# TPadTabletBattery.net
KiCad netlist of a schematic drawn in EAGLE
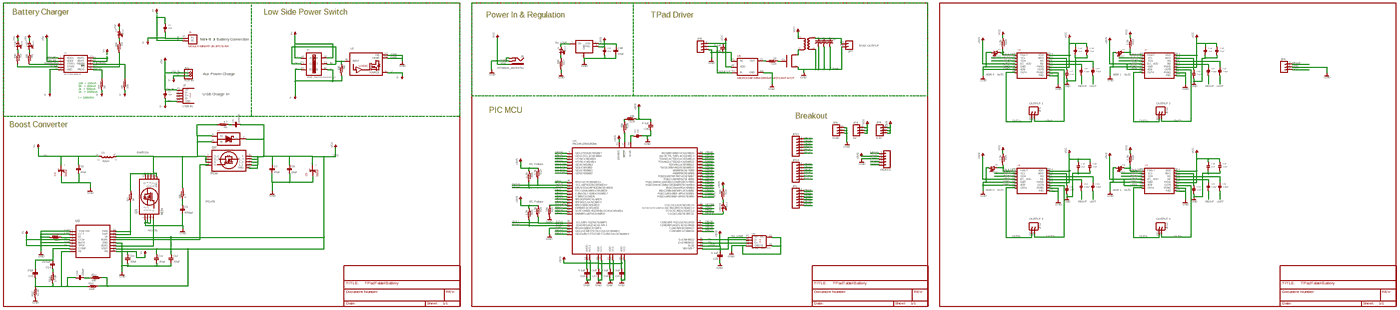
[diagram p0: schematic, sheet 1, overview]
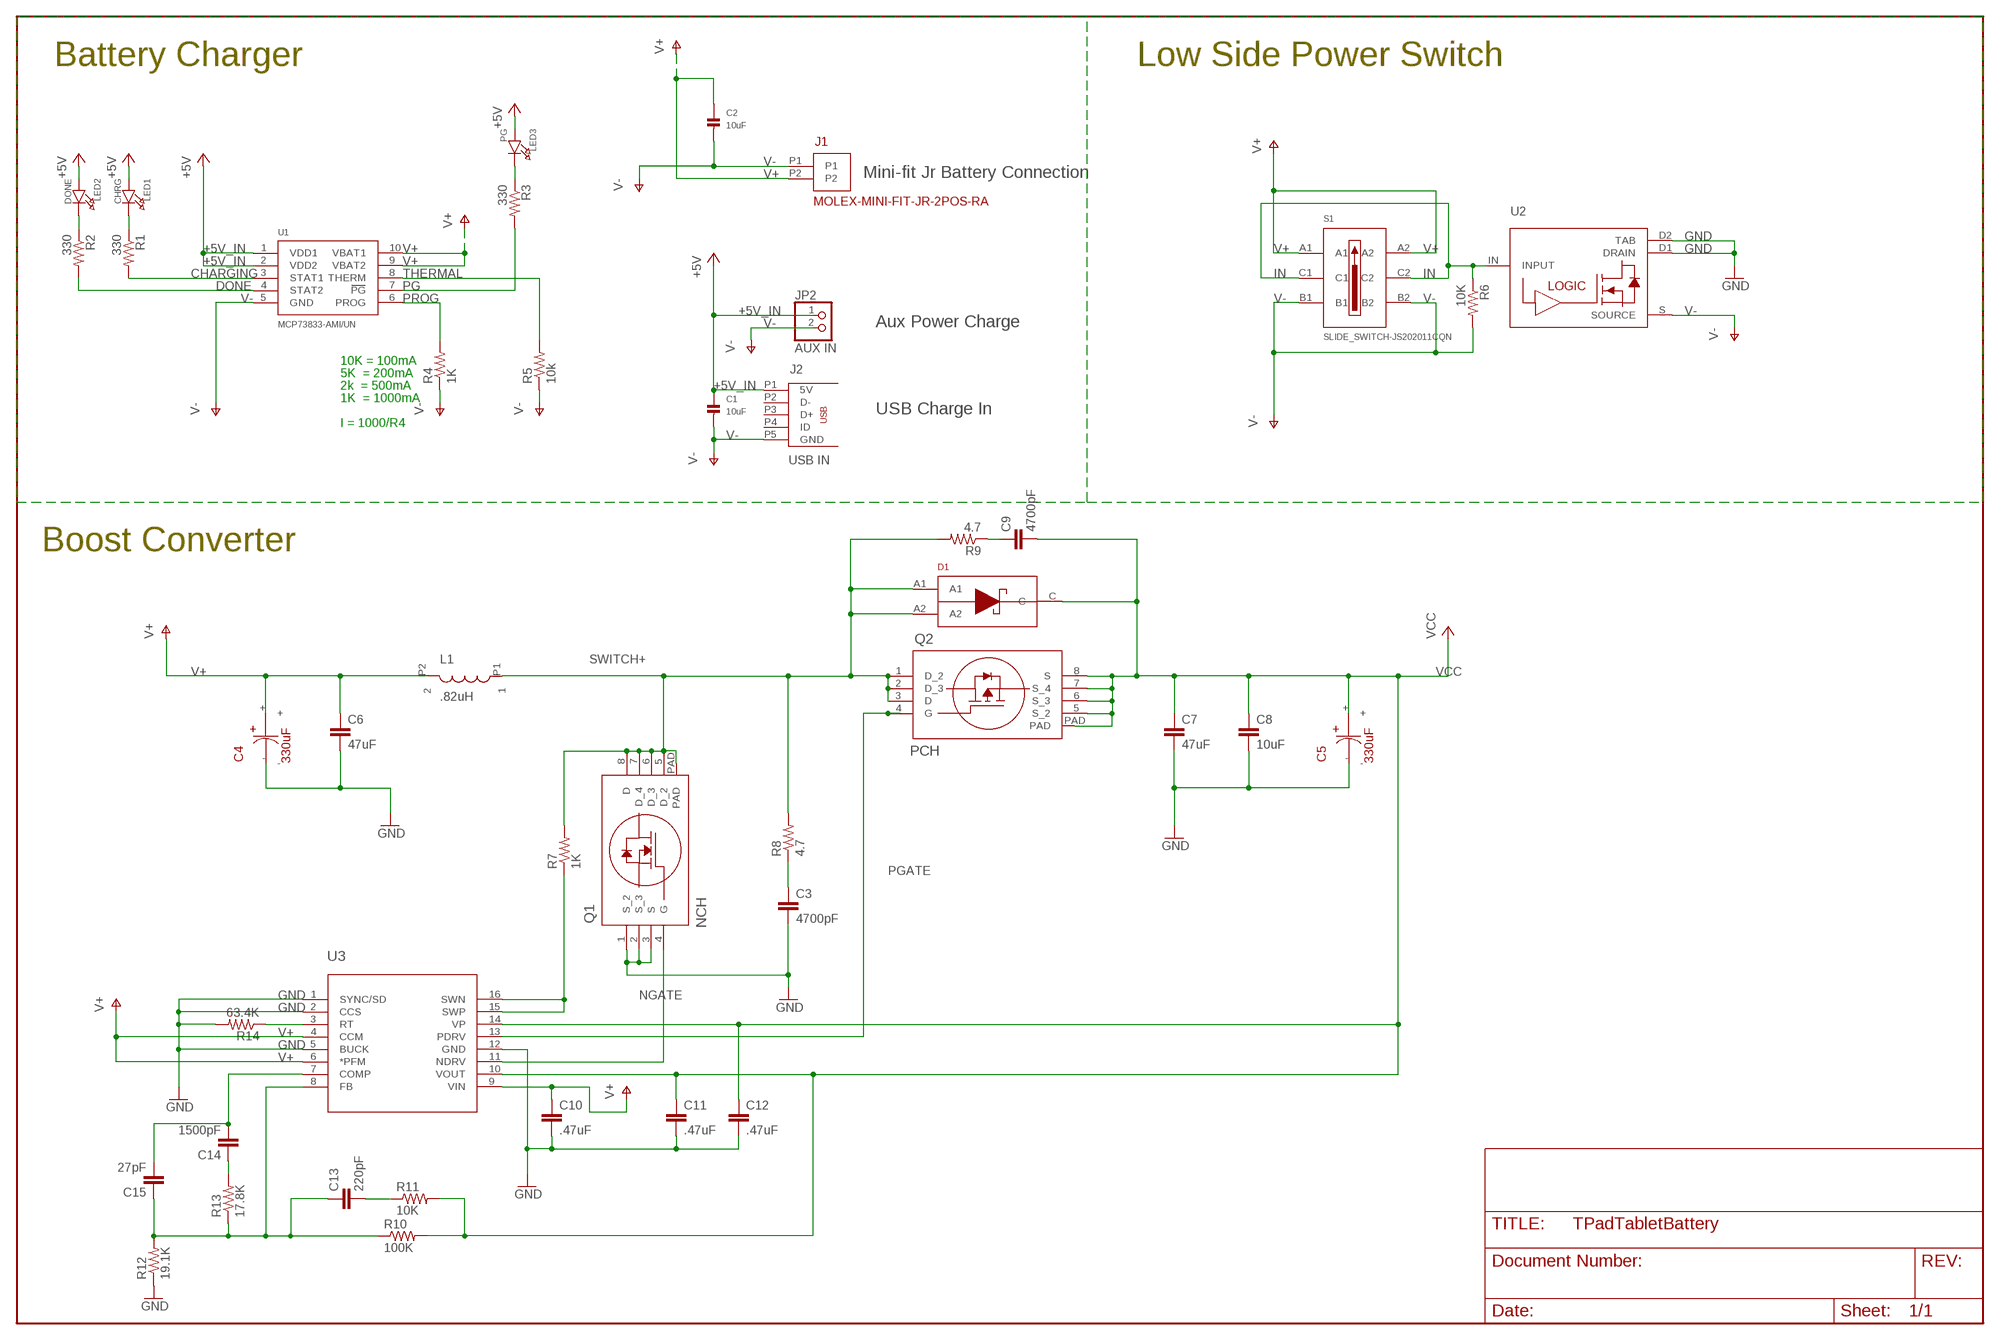
[diagram p1: schematic, sheet 1, part 1 of 4]
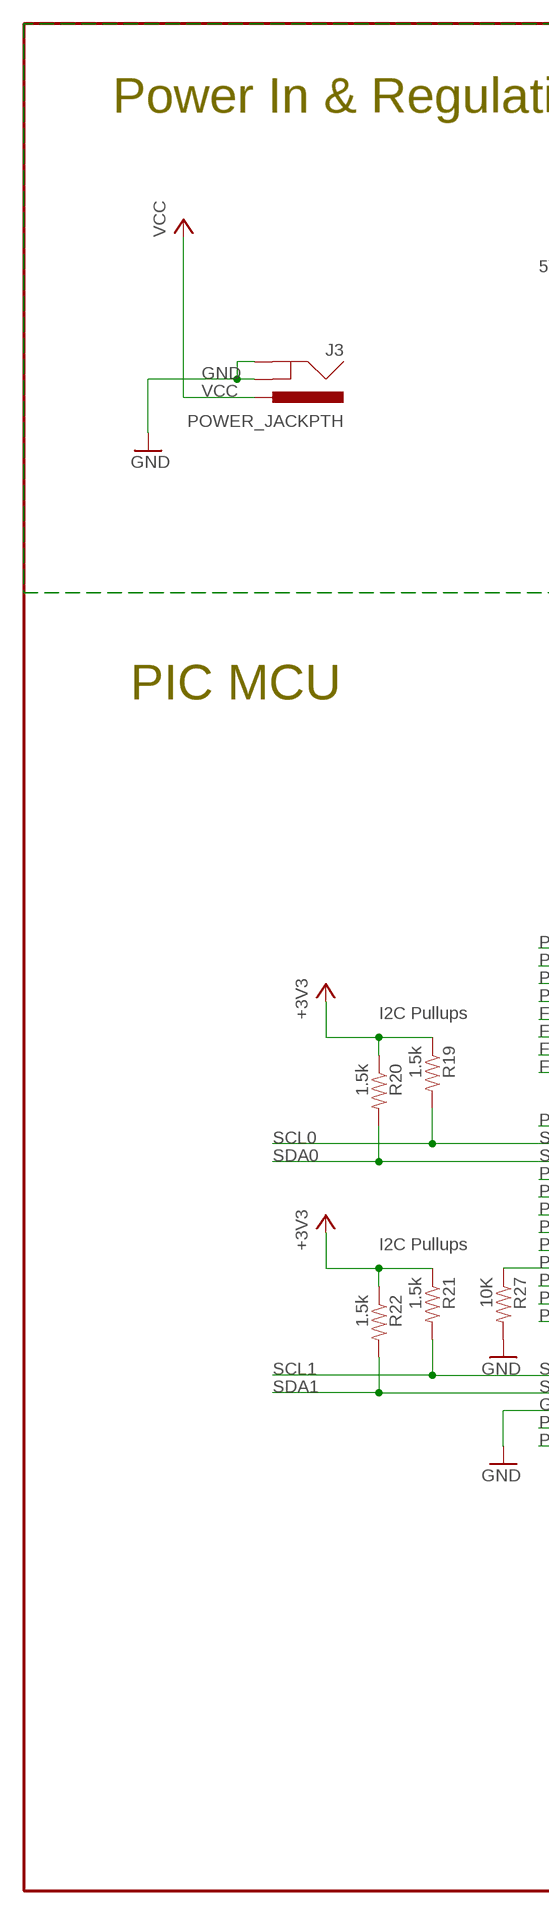
[diagram p2: schematic, sheet 1, part 2 of 4]
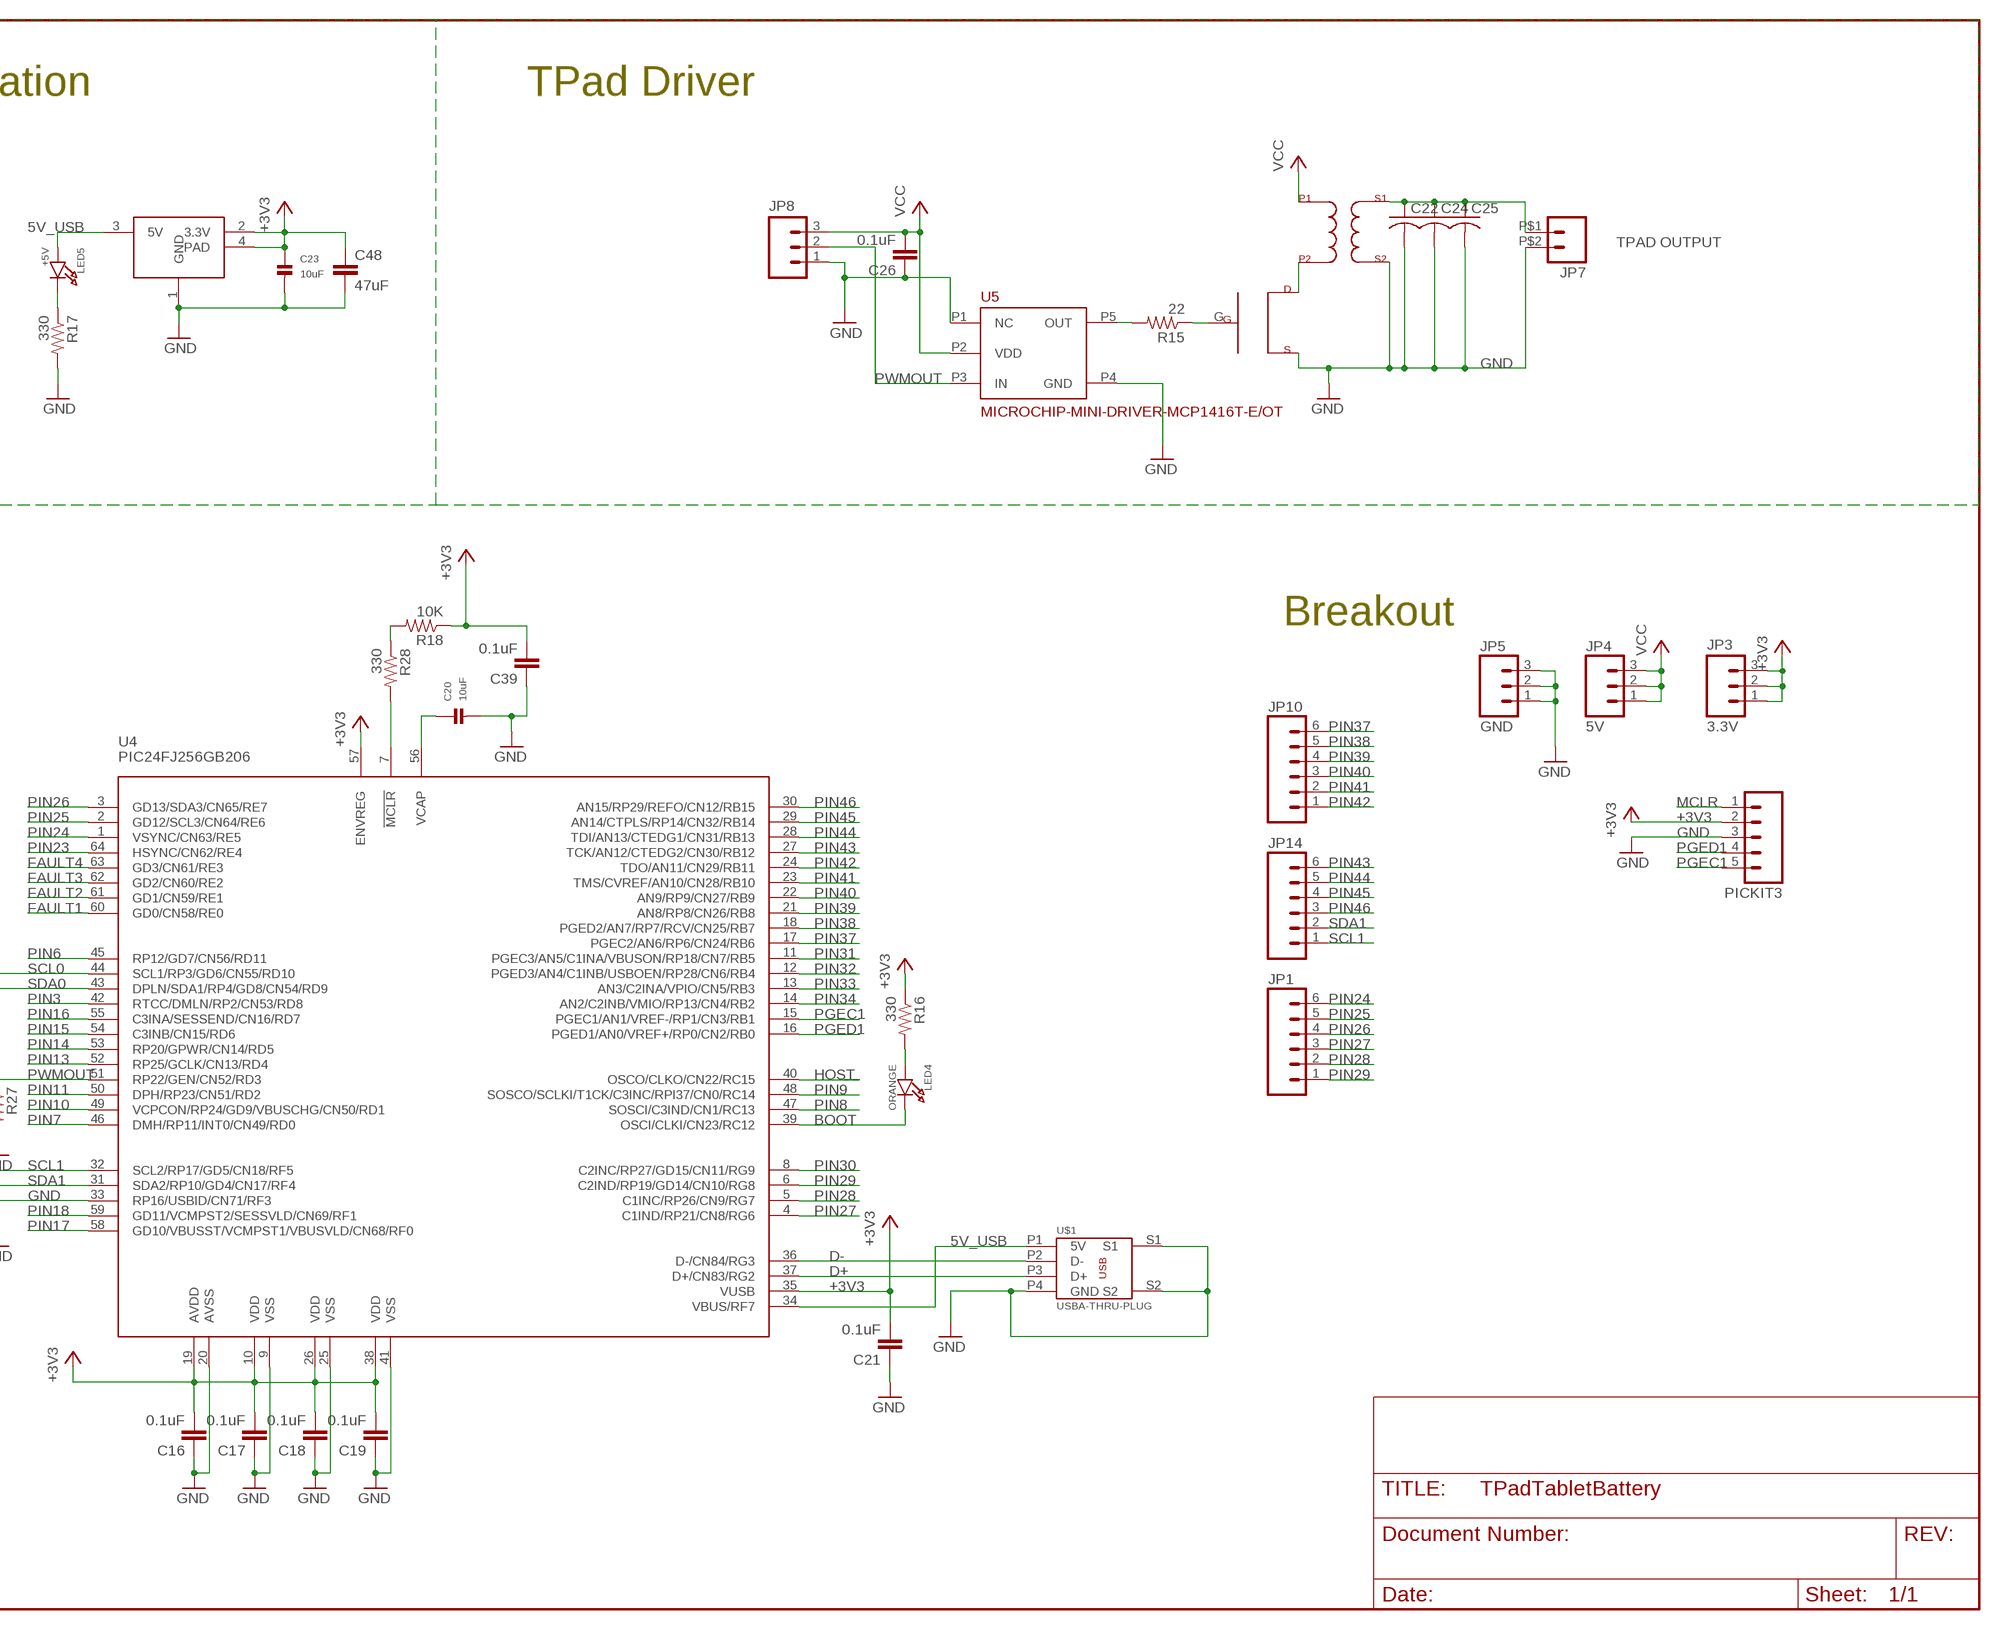
[diagram p3: schematic, sheet 1, part 3 of 4]
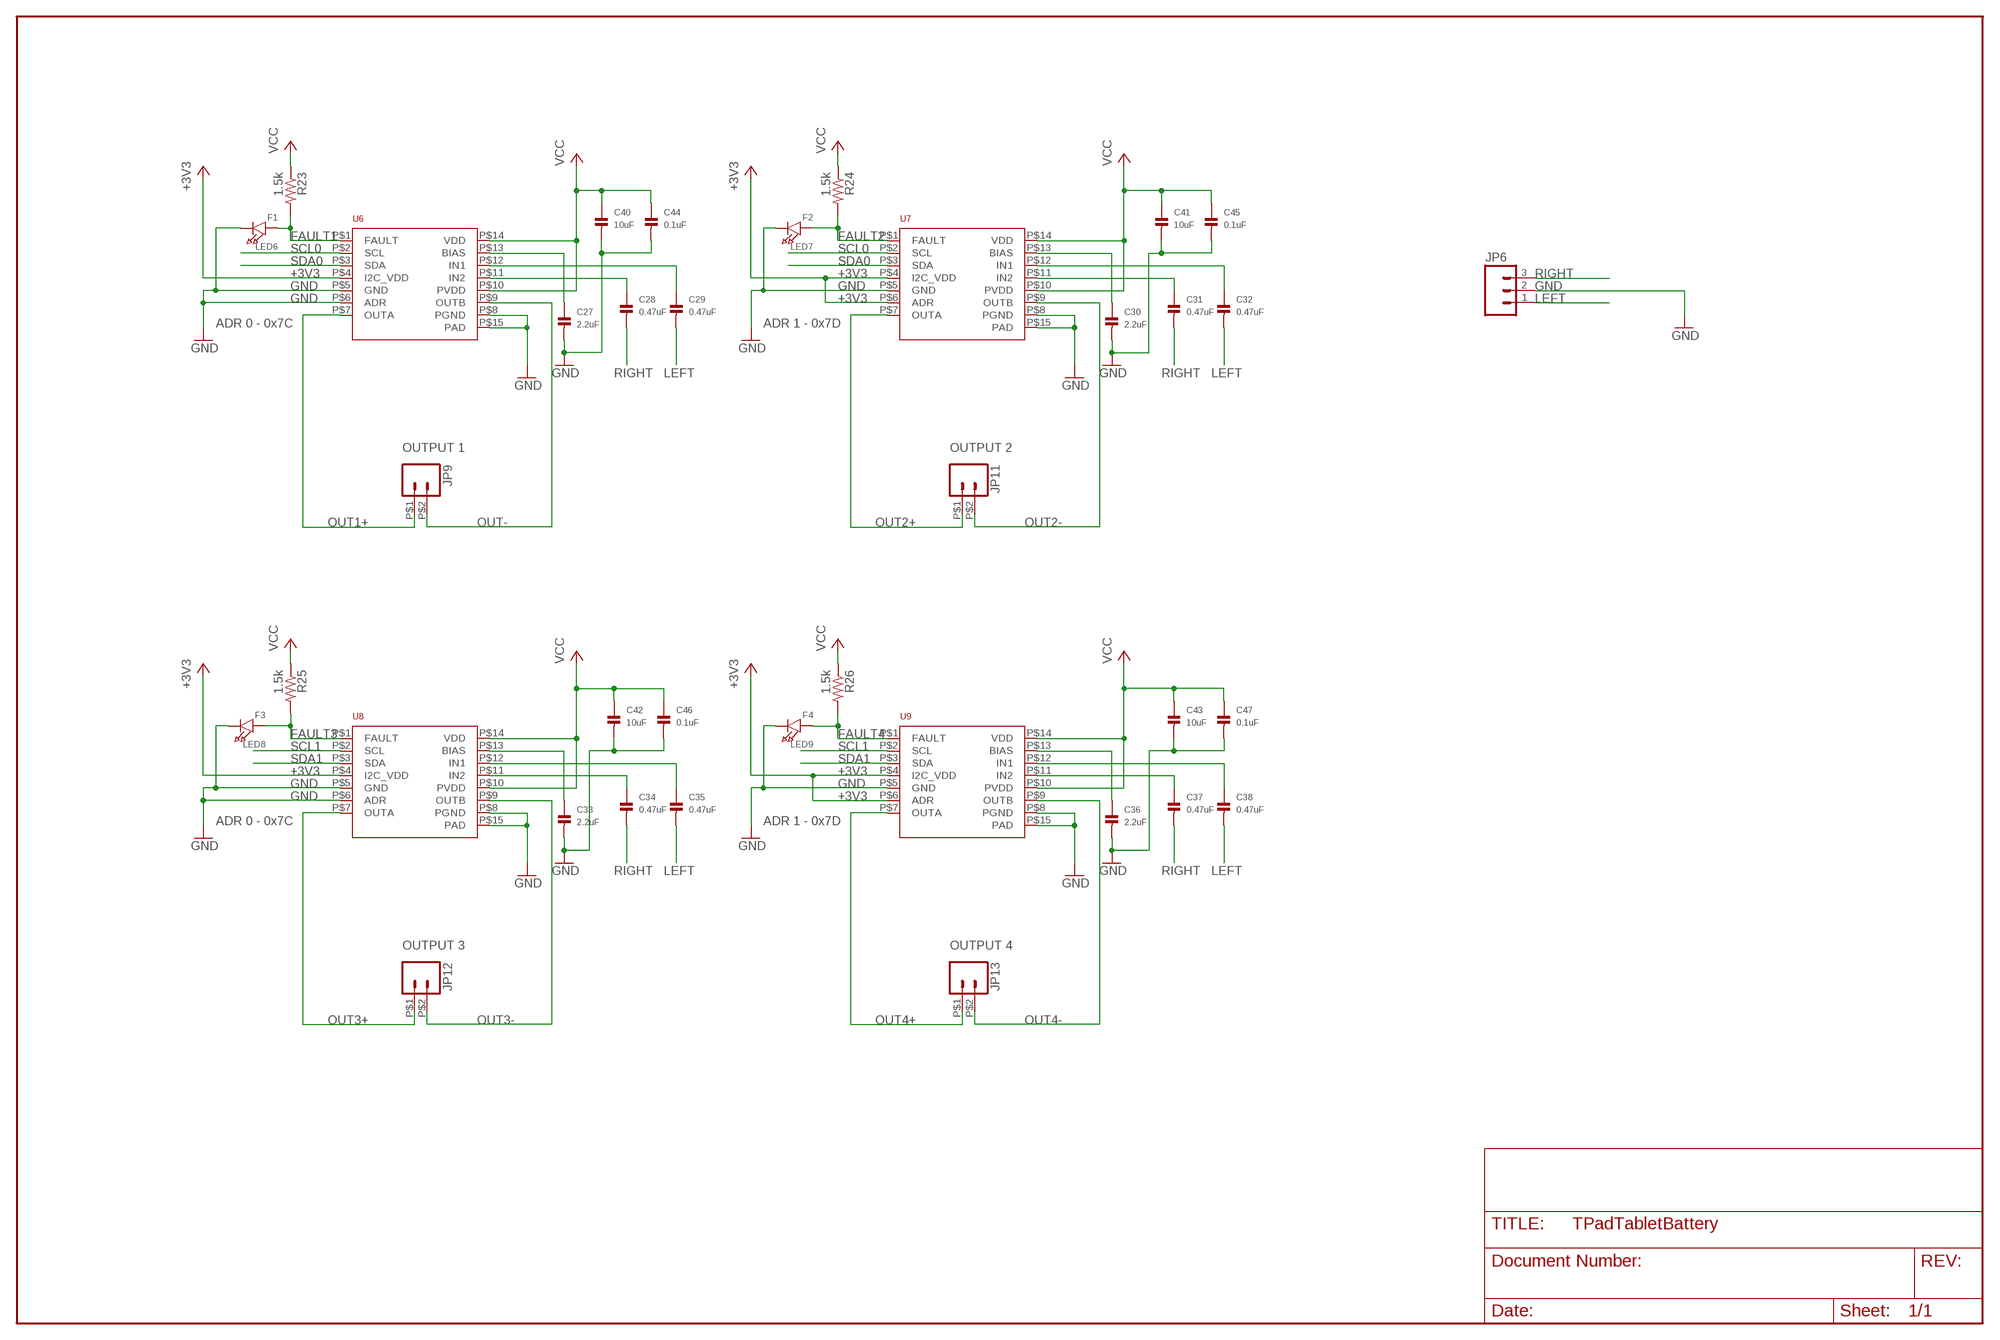
[diagram p4: schematic, sheet 1, part 4 of 4]

(export (version "E")
  (design (tool "Eeschema 10.0.6"))
  (components
    (comp (ref "C1")
      (value "10uF")
      (footprint "eagle-import:MICROBUILDER_0805")
      (libsource (lib "eagle-import") (part "MICROBUILDER_CAP_CERAMIC0805"))
    )
    (comp (ref "C2")
      (value "10uF")
      (footprint "eagle-import:MICROBUILDER_0805")
      (libsource (lib "eagle-import") (part "MICROBUILDER_CAP_CERAMIC0805"))
    )
    (comp (ref "C3")
      (value "4700pF")
      (footprint "eagle-import:0603-CAP")
      (libsource (lib "eagle-import") (part "CAP0603-CAP"))
    )
    (comp (ref "C4")
      (value "330uF")
      (footprint "eagle-import:330UF_POSCAP")
      (libsource (lib "eagle-import") (part "330UF_POSCAP"))
    )
    (comp (ref "C5")
      (value "330uF")
      (footprint "eagle-import:330UF_POSCAP")
      (libsource (lib "eagle-import") (part "330UF_POSCAP"))
    )
    (comp (ref "C6")
      (value "47uF")
      (footprint "eagle-import:1210")
      (libsource (lib "eagle-import") (part "CAP1210"))
    )
    (comp (ref "C7")
      (value "47uF")
      (footprint "eagle-import:1210")
      (libsource (lib "eagle-import") (part "CAP1210"))
    )
    (comp (ref "C8")
      (value "10uF")
      (footprint "eagle-import:0805")
      (libsource (lib "eagle-import") (part "CAP0805"))
    )
    (comp (ref "C9")
      (value "4700pF")
      (footprint "eagle-import:0603-CAP")
      (libsource (lib "eagle-import") (part "CAP0603-CAP"))
    )
    (comp (ref "C10")
      (value ".47uF")
      (footprint "eagle-import:0603-CAP")
      (libsource (lib "eagle-import") (part "CAP0603-CAP"))
    )
    (comp (ref "C11")
      (value ".47uF")
      (footprint "eagle-import:0603-CAP")
      (libsource (lib "eagle-import") (part "CAP0603-CAP"))
    )
    (comp (ref "C12")
      (value ".47uF")
      (footprint "eagle-import:0603-CAP")
      (libsource (lib "eagle-import") (part "CAP0603-CAP"))
    )
    (comp (ref "C13")
      (value "220pF")
      (footprint "eagle-import:0603-CAP")
      (libsource (lib "eagle-import") (part "CAP0603-CAP"))
    )
    (comp (ref "C14")
      (value "1500pF")
      (footprint "eagle-import:0603-CAP")
      (libsource (lib "eagle-import") (part "CAP0603-CAP"))
    )
    (comp (ref "C15")
      (value "27pF")
      (footprint "eagle-import:0603-CAP")
      (libsource (lib "eagle-import") (part "CAP0603-CAP"))
    )
    (comp (ref "C16")
      (value "0.1uF")
      (footprint "eagle-import:0603-CAP")
      (libsource (lib "eagle-import") (part "CAP0603-CAP"))
    )
    (comp (ref "C17")
      (value "0.1uF")
      (footprint "eagle-import:0603-CAP")
      (libsource (lib "eagle-import") (part "CAP0603-CAP"))
    )
    (comp (ref "C18")
      (value "0.1uF")
      (footprint "eagle-import:0603-CAP")
      (libsource (lib "eagle-import") (part "CAP0603-CAP"))
    )
    (comp (ref "C19")
      (value "0.1uF")
      (footprint "eagle-import:0603-CAP")
      (libsource (lib "eagle-import") (part "CAP0603-CAP"))
    )
    (comp (ref "C20")
      (value "10uF")
      (footprint "eagle-import:MICROBUILDER_0805")
      (libsource (lib "eagle-import") (part "MICROBUILDER_CAP_CERAMIC0805"))
    )
    (comp (ref "C21")
      (value "0.1uF")
      (footprint "eagle-import:0603-CAP")
      (libsource (lib "eagle-import") (part "CAP0603-CAP"))
    )
    (comp (ref "C22")
      (value "C-US050-035X075")
      (footprint "eagle-import:C050-035X075")
      (libsource (lib "eagle-import") (part "C-US050-035X075"))
    )
    (comp (ref "C23")
      (value "10uF")
      (footprint "eagle-import:MICROBUILDER_0805")
      (libsource (lib "eagle-import") (part "MICROBUILDER_CAP_CERAMIC0805"))
    )
    (comp (ref "C24")
      (value "C-US050-035X075")
      (footprint "eagle-import:C050-035X075")
      (libsource (lib "eagle-import") (part "C-US050-035X075"))
    )
    (comp (ref "C25")
      (value "C-US050-035X075")
      (footprint "eagle-import:C050-035X075")
      (libsource (lib "eagle-import") (part "C-US050-035X075"))
    )
    (comp (ref "C26")
      (value "0.1uF")
      (footprint "eagle-import:0603-CAP")
      (libsource (lib "eagle-import") (part "CAP0603-CAP"))
    )
    (comp (ref "C27")
      (value "2.2uF")
      (footprint "eagle-import:MICROBUILDER_0603")
      (libsource (lib "eagle-import") (part "MICROBUILDER_CAP_CERAMIC0603"))
    )
    (comp (ref "C28")
      (value "0.47uF")
      (footprint "eagle-import:MICROBUILDER_0603")
      (libsource (lib "eagle-import") (part "MICROBUILDER_CAP_CERAMIC0603"))
    )
    (comp (ref "C29")
      (value "0.47uF")
      (footprint "eagle-import:MICROBUILDER_0603")
      (libsource (lib "eagle-import") (part "MICROBUILDER_CAP_CERAMIC0603"))
    )
    (comp (ref "C30")
      (value "2.2uF")
      (footprint "eagle-import:MICROBUILDER_0603")
      (libsource (lib "eagle-import") (part "MICROBUILDER_CAP_CERAMIC0603"))
    )
    (comp (ref "C31")
      (value "0.47uF")
      (footprint "eagle-import:MICROBUILDER_0603")
      (libsource (lib "eagle-import") (part "MICROBUILDER_CAP_CERAMIC0603"))
    )
    (comp (ref "C32")
      (value "0.47uF")
      (footprint "eagle-import:MICROBUILDER_0603")
      (libsource (lib "eagle-import") (part "MICROBUILDER_CAP_CERAMIC0603"))
    )
    (comp (ref "C33")
      (value "2.2uF")
      (footprint "eagle-import:MICROBUILDER_0603")
      (libsource (lib "eagle-import") (part "MICROBUILDER_CAP_CERAMIC0603"))
    )
    (comp (ref "C34")
      (value "0.47uF")
      (footprint "eagle-import:MICROBUILDER_0603")
      (libsource (lib "eagle-import") (part "MICROBUILDER_CAP_CERAMIC0603"))
    )
    (comp (ref "C35")
      (value "0.47uF")
      (footprint "eagle-import:MICROBUILDER_0603")
      (libsource (lib "eagle-import") (part "MICROBUILDER_CAP_CERAMIC0603"))
    )
    (comp (ref "C36")
      (value "2.2uF")
      (footprint "eagle-import:MICROBUILDER_0603")
      (libsource (lib "eagle-import") (part "MICROBUILDER_CAP_CERAMIC0603"))
    )
    (comp (ref "C37")
      (value "0.47uF")
      (footprint "eagle-import:MICROBUILDER_0603")
      (libsource (lib "eagle-import") (part "MICROBUILDER_CAP_CERAMIC0603"))
    )
    (comp (ref "C38")
      (value "0.47uF")
      (footprint "eagle-import:MICROBUILDER_0603")
      (libsource (lib "eagle-import") (part "MICROBUILDER_CAP_CERAMIC0603"))
    )
    (comp (ref "C39")
      (value "0.1uF")
      (footprint "eagle-import:0603-CAP")
      (libsource (lib "eagle-import") (part "CAP0603-CAP"))
    )
    (comp (ref "C40")
      (value "10uF")
      (footprint "eagle-import:MICROBUILDER_0805")
      (libsource (lib "eagle-import") (part "MICROBUILDER_CAP_CERAMIC0805"))
    )
    (comp (ref "C41")
      (value "10uF")
      (footprint "eagle-import:MICROBUILDER_0805")
      (libsource (lib "eagle-import") (part "MICROBUILDER_CAP_CERAMIC0805"))
    )
    (comp (ref "C42")
      (value "10uF")
      (footprint "eagle-import:MICROBUILDER_0805")
      (libsource (lib "eagle-import") (part "MICROBUILDER_CAP_CERAMIC0805"))
    )
    (comp (ref "C43")
      (value "10uF")
      (footprint "eagle-import:MICROBUILDER_0805")
      (libsource (lib "eagle-import") (part "MICROBUILDER_CAP_CERAMIC0805"))
    )
    (comp (ref "C44")
      (value "0.1uF")
      (footprint "eagle-import:MICROBUILDER_0603")
      (libsource (lib "eagle-import") (part "MICROBUILDER_CAP_CERAMIC0603"))
    )
    (comp (ref "C45")
      (value "0.1uF")
      (footprint "eagle-import:MICROBUILDER_0603")
      (libsource (lib "eagle-import") (part "MICROBUILDER_CAP_CERAMIC0603"))
    )
    (comp (ref "C46")
      (value "0.1uF")
      (footprint "eagle-import:MICROBUILDER_0603")
      (libsource (lib "eagle-import") (part "MICROBUILDER_CAP_CERAMIC0603"))
    )
    (comp (ref "C47")
      (value "0.1uF")
      (footprint "eagle-import:MICROBUILDER_0603")
      (libsource (lib "eagle-import") (part "MICROBUILDER_CAP_CERAMIC0603"))
    )
    (comp (ref "C48")
      (value "47uF")
      (footprint "eagle-import:1210")
      (libsource (lib "eagle-import") (part "CAP1210"))
    )
    (comp (ref "D1")
      (value "POWER-DIODE_PDS835L")
      (footprint "eagle-import:POWER-DIODE_PDS835L")
      (libsource (lib "eagle-import") (part "POWER-DIODE_PDS835L"))
    )
    (comp (ref "J1")
      (value "MOLEX-MINI-FIT-JR-2POS-RA")
      (footprint "eagle-import:MOLEX-MINI-FIT-JR-2POS-RA")
      (libsource (lib "eagle-import") (part "MOLEX-MINI-FIT-JR-2POS-RA"))
    )
    (comp (ref "J2")
      (value "USB IN")
      (footprint "eagle-import:USBMICROBSMT")
      (libsource (lib "eagle-import") (part "USBMICROB"))
    )
    (comp (ref "J3")
      (value "POWER_JACKPTH")
      (footprint "eagle-import:POWER_JACK_PTH")
      (libsource (lib "eagle-import") (part "POWER_JACKPTH"))
    )
    (comp (ref "JP1")
      (value "M06SIP")
      (footprint "eagle-import:1X06")
      (libsource (lib "eagle-import") (part "M06SIP"))
    )
    (comp (ref "JP2")
      (value "AUX IN")
      (footprint "eagle-import:MICROBUILDER_1X02_ROUND")
      (libsource (lib "eagle-import") (part "MICROBUILDER_HEADER-1X2ROUND"))
    )
    (comp (ref "JP3")
      (value "3.3V")
      (footprint "eagle-import:1X03")
      (libsource (lib "eagle-import") (part "M03PTH"))
    )
    (comp (ref "JP4")
      (value "5V")
      (footprint "eagle-import:1X03")
      (libsource (lib "eagle-import") (part "M03PTH"))
    )
    (comp (ref "JP5")
      (value "GND")
      (footprint "eagle-import:1X03")
      (libsource (lib "eagle-import") (part "M03PTH"))
    )
    (comp (ref "JP6")
      (value "M03PTH")
      (footprint "eagle-import:1X03")
      (libsource (lib "eagle-import") (part "M03PTH"))
    )
    (comp (ref "JP7")
      (value "M02PTH2")
      (footprint "eagle-import:1X02_BIG")
      (libsource (lib "eagle-import") (part "M02PTH2"))
    )
    (comp (ref "JP8")
      (value "M03PTH")
      (footprint "eagle-import:1X03")
      (libsource (lib "eagle-import") (part "M03PTH"))
    )
    (comp (ref "JP9")
      (value "M02PTH2")
      (footprint "eagle-import:1X02_BIG")
      (libsource (lib "eagle-import") (part "M02PTH2"))
    )
    (comp (ref "JP10")
      (value "M06SIP")
      (footprint "eagle-import:1X06")
      (libsource (lib "eagle-import") (part "M06SIP"))
    )
    (comp (ref "JP11")
      (value "M02PTH2")
      (footprint "eagle-import:1X02_BIG")
      (libsource (lib "eagle-import") (part "M02PTH2"))
    )
    (comp (ref "JP12")
      (value "M02PTH2")
      (footprint "eagle-import:1X02_BIG")
      (libsource (lib "eagle-import") (part "M02PTH2"))
    )
    (comp (ref "JP13")
      (value "M02PTH2")
      (footprint "eagle-import:1X02_BIG")
      (libsource (lib "eagle-import") (part "M02PTH2"))
    )
    (comp (ref "JP14")
      (value "M06SIP")
      (footprint "eagle-import:1X06")
      (libsource (lib "eagle-import") (part "M06SIP"))
    )
    (comp (ref "L1")
      (value ".82uH")
      (footprint "eagle-import:.82UH_INDUCTOR-IHLP3232DZERR82M01")
      (libsource (lib "eagle-import") (part ".82UH_INDUCTOR-IHLP3232DZERR82M01"))
    )
    (comp (ref "LED1")
      (value "CHRG")
      (footprint "eagle-import:MICROBUILDER_CHIPLED_0603")
      (libsource (lib "eagle-import") (part "MICROBUILDER_LED0603"))
    )
    (comp (ref "LED2")
      (value "DONE")
      (footprint "eagle-import:MICROBUILDER_CHIPLED_0603")
      (libsource (lib "eagle-import") (part "MICROBUILDER_LED0603"))
    )
    (comp (ref "LED3")
      (value "PG")
      (footprint "eagle-import:MICROBUILDER_CHIPLED_0603")
      (libsource (lib "eagle-import") (part "MICROBUILDER_LED0603"))
    )
    (comp (ref "LED4")
      (value "ORANGE")
      (footprint "eagle-import:MICROBUILDER_CHIPLED_0603")
      (libsource (lib "eagle-import") (part "MICROBUILDER_LED0603"))
    )
    (comp (ref "LED5")
      (value "+5V")
      (footprint "eagle-import:MICROBUILDER_CHIPLED_0603")
      (libsource (lib "eagle-import") (part "MICROBUILDER_LED0603"))
    )
    (comp (ref "LED6")
      (value "F1")
      (footprint "eagle-import:MICROBUILDER_CHIPLED_0603")
      (libsource (lib "eagle-import") (part "MICROBUILDER_LED0603"))
    )
    (comp (ref "LED7")
      (value "F2")
      (footprint "eagle-import:MICROBUILDER_CHIPLED_0603")
      (libsource (lib "eagle-import") (part "MICROBUILDER_LED0603"))
    )
    (comp (ref "LED8")
      (value "F3")
      (footprint "eagle-import:MICROBUILDER_CHIPLED_0603")
      (libsource (lib "eagle-import") (part "MICROBUILDER_LED0603"))
    )
    (comp (ref "LED9")
      (value "F4")
      (footprint "eagle-import:MICROBUILDER_CHIPLED_0603")
      (libsource (lib "eagle-import") (part "MICROBUILDER_LED0603"))
    )
    (comp (ref "PICKIT3")
      (value "M05PTH")
      (footprint "eagle-import:1X05")
      (libsource (lib "eagle-import") (part "M05PTH"))
    )
    (comp (ref "Q1")
      (value "NCH")
      (footprint "eagle-import:DQG8")
      (fields
        (field (name "GENERIC_PART_NUMBER") "CSD16340Q3")
        (field (name "MANUFACTURER") "Texas Instruments")
      )
      (libsource (lib "eagle-import") (part "NCH-MOSFET_CSD16340Q3"))
    )
    (comp (ref "Q2")
      (value "PCH")
      (footprint "eagle-import:DQG8")
      (fields
        (field (name "GENERIC_PART_NUMBER") "CSD25401Q3")
        (field (name "MANUFACTURER") "Texas Instruments")
      )
      (libsource (lib "eagle-import") (part "PCH-MOSFET_CSD25401Q3"))
    )
    (comp (ref "R1")
      (value "330")
      (footprint "eagle-import:0603-RES")
      (libsource (lib "eagle-import") (part "RESISTOR0603-RES"))
    )
    (comp (ref "R2")
      (value "330")
      (footprint "eagle-import:0603-RES")
      (libsource (lib "eagle-import") (part "RESISTOR0603-RES"))
    )
    (comp (ref "R3")
      (value "330")
      (footprint "eagle-import:0603-RES")
      (libsource (lib "eagle-import") (part "RESISTOR0603-RES"))
    )
    (comp (ref "R4")
      (value "1K")
      (footprint "eagle-import:0805")
      (libsource (lib "eagle-import") (part "RESISTOR0805-RES"))
    )
    (comp (ref "R5")
      (value "10k")
      (footprint "eagle-import:0805")
      (libsource (lib "eagle-import") (part "RESISTOR0805-RES"))
    )
    (comp (ref "R6")
      (value "10K")
      (footprint "eagle-import:0603-RES")
      (libsource (lib "eagle-import") (part "RESISTOR0603-RES"))
    )
    (comp (ref "R7")
      (value "1K")
      (footprint "eagle-import:0603-RES")
      (libsource (lib "eagle-import") (part "RESISTOR0603-RES"))
    )
    (comp (ref "R8")
      (value "4.7")
      (footprint "eagle-import:0603-RES")
      (libsource (lib "eagle-import") (part "RESISTOR0603-RES"))
    )
    (comp (ref "R9")
      (value "4.7")
      (footprint "eagle-import:0603-RES")
      (libsource (lib "eagle-import") (part "RESISTOR0603-RES"))
    )
    (comp (ref "R10")
      (value "100K")
      (footprint "eagle-import:0603-RES")
      (libsource (lib "eagle-import") (part "RESISTOR0603-RES"))
    )
    (comp (ref "R11")
      (value "10K")
      (footprint "eagle-import:0603-RES")
      (libsource (lib "eagle-import") (part "RESISTOR0603-RES"))
    )
    (comp (ref "R12")
      (value "19.1K")
      (footprint "eagle-import:0603-RES")
      (libsource (lib "eagle-import") (part "RESISTOR0603-RES"))
    )
    (comp (ref "R13")
      (value "17.8K")
      (footprint "eagle-import:0603-RES")
      (libsource (lib "eagle-import") (part "RESISTOR0603-RES"))
    )
    (comp (ref "R14")
      (value "63.4K")
      (footprint "eagle-import:0603-RES")
      (libsource (lib "eagle-import") (part "RESISTOR0603-RES"))
    )
    (comp (ref "R15")
      (value "22")
      (footprint "eagle-import:0603-RES")
      (libsource (lib "eagle-import") (part "RESISTOR0603-RES"))
    )
    (comp (ref "R16")
      (value "330")
      (footprint "eagle-import:0603-RES")
      (libsource (lib "eagle-import") (part "RESISTOR0603-RES"))
    )
    (comp (ref "R17")
      (value "330")
      (footprint "eagle-import:0603-RES")
      (libsource (lib "eagle-import") (part "RESISTOR0603-RES"))
    )
    (comp (ref "R18")
      (value "10K")
      (footprint "eagle-import:0603-RES")
      (libsource (lib "eagle-import") (part "RESISTOR0603-RES"))
    )
    (comp (ref "R19")
      (value "1.5k")
      (footprint "eagle-import:0603-RES")
      (libsource (lib "eagle-import") (part "RESISTOR0603-RES"))
    )
    (comp (ref "R20")
      (value "1.5k")
      (footprint "eagle-import:0603-RES")
      (libsource (lib "eagle-import") (part "RESISTOR0603-RES"))
    )
    (comp (ref "R21")
      (value "1.5k")
      (footprint "eagle-import:0603-RES")
      (libsource (lib "eagle-import") (part "RESISTOR0603-RES"))
    )
    (comp (ref "R22")
      (value "1.5k")
      (footprint "eagle-import:0603-RES")
      (libsource (lib "eagle-import") (part "RESISTOR0603-RES"))
    )
    (comp (ref "R23")
      (value "1.5k")
      (footprint "eagle-import:0603-RES")
      (libsource (lib "eagle-import") (part "RESISTOR0603-RES"))
    )
    (comp (ref "R24")
      (value "1.5k")
      (footprint "eagle-import:0603-RES")
      (libsource (lib "eagle-import") (part "RESISTOR0603-RES"))
    )
    (comp (ref "R25")
      (value "1.5k")
      (footprint "eagle-import:0603-RES")
      (libsource (lib "eagle-import") (part "RESISTOR0603-RES"))
    )
    (comp (ref "R26")
      (value "1.5k")
      (footprint "eagle-import:0603-RES")
      (libsource (lib "eagle-import") (part "RESISTOR0603-RES"))
    )
    (comp (ref "R27")
      (value "10K")
      (footprint "eagle-import:0603-RES")
      (libsource (lib "eagle-import") (part "RESISTOR0603-RES"))
    )
    (comp (ref "R28")
      (value "330")
      (footprint "eagle-import:0603-RES")
      (libsource (lib "eagle-import") (part "RESISTOR0603-RES"))
    )
    (comp (ref "S1")
      (value "SLIDE_SWITCH-JS202011CQN")
      (footprint "eagle-import:SLIDE_SWITCH-JS202011CQN")
      (libsource (lib "eagle-import") (part "SLIDE_SWITCH-JS202011CQN"))
    )
    (comp (ref "U$1")
      (value "USBA-THRU-PLUG")
      (footprint "eagle-import:USBA-THRU-FLUG")
      (libsource (lib "eagle-import") (part "USBA-THRU-PLUG"))
    )
    (comp (ref "U$4")
      (value "TRANSFORMER")
      (footprint "eagle-import:TRANSFORMER")
      (libsource (lib "eagle-import") (part "TRANSFORMER"))
    )
    (comp (ref "U$5")
      (value "TPAD_IRF520N")
      (footprint "eagle-import:TPAD_TO220")
      (libsource (lib "eagle-import") (part "TPAD_IRF520N"))
    )
    (comp (ref "U$6")
      (value "LD33V")
      (footprint "eagle-import:SOT223")
      (libsource (lib "eagle-import") (part "LD33V"))
    )
    (comp (ref "U1")
      (value "MCP73833-AMI/UN")
      (footprint "eagle-import:MICROBUILDER_MSOP10")
      (libsource (lib "eagle-import") (part "MICROBUILDER_MCP73833"))
    )
    (comp (ref "U2")
      (value "STM-LOW-SWITCH-VNL5050N3TR-E")
      (footprint "eagle-import:SOT223")
      (libsource (lib "eagle-import") (part "STM-LOW-SWITCH-VNL5050N3TR-E"))
    )
    (comp (ref "U3")
      (value "TPS43000_PW_16")
      (footprint "eagle-import:PW16")
      (fields
        (field (name "GENERIC_PART_NUMBER") "TPS43000")
        (field (name "MANUFACTURER") "Texas Instruments")
        (field (name "MANUFACTURER_PART_NUMBER") "tps43000_pw_16")
      )
      (libsource (lib "eagle-import") (part "TPS43000_PW_16"))
    )
    (comp (ref "U4")
      (value "PIC24FJ256GB206")
      (footprint "eagle-import:PIC24FXXX_TQFP64")
      (libsource (lib "eagle-import") (part "PIC24FXXXDAX06"))
    )
    (comp (ref "U5")
      (value "MICROCHIP-MINI-DRIVER-MCP1416T-E/OT")
      (footprint "eagle-import:MICROCHIP-MINI-DRIVER-MCP1416T-E_OT")
      (libsource (lib "eagle-import") (part "MICROCHIP-MINI-DRIVER-MCP1416T-E/OT"))
    )
    (comp (ref "U6")
      (value "TI-AUDIOAMP-LM48100Q")
      (footprint "eagle-import:TI-AUDIOAMP-LM48100Q")
      (libsource (lib "eagle-import") (part "TI-AUDIOAMP-LM48100Q"))
    )
    (comp (ref "U7")
      (value "TI-AUDIOAMP-LM48100Q")
      (footprint "eagle-import:TI-AUDIOAMP-LM48100Q")
      (libsource (lib "eagle-import") (part "TI-AUDIOAMP-LM48100Q"))
    )
    (comp (ref "U8")
      (value "TI-AUDIOAMP-LM48100Q")
      (footprint "eagle-import:TI-AUDIOAMP-LM48100Q")
      (libsource (lib "eagle-import") (part "TI-AUDIOAMP-LM48100Q"))
    )
    (comp (ref "U9")
      (value "TI-AUDIOAMP-LM48100Q")
      (footprint "eagle-import:TI-AUDIOAMP-LM48100Q")
      (libsource (lib "eagle-import") (part "TI-AUDIOAMP-LM48100Q"))
    )
  )
  (nets
    (net (code "1") (name "+3V3") (class "Default")
      (node (ref "C16") (pin "2") (pinfunction "2_2") (pintype "passive"))
      (node (ref "C17") (pin "2") (pinfunction "2_2") (pintype "passive"))
      (node (ref "C18") (pin "2") (pinfunction "2_2") (pintype "passive"))
      (node (ref "C19") (pin "2") (pinfunction "2_2") (pintype "passive"))
      (node (ref "C21") (pin "2") (pinfunction "2_2") (pintype "passive"))
      (node (ref "C23") (pin "1") (pinfunction "P$1_1") (pintype "passive"))
      (node (ref "C39") (pin "2") (pinfunction "2_2") (pintype "passive"))
      (node (ref "C48") (pin "1") (pinfunction "1_1") (pintype "passive"))
      (node (ref "JP3") (pin "1") (pinfunction "1_1") (pintype "passive"))
      (node (ref "JP3") (pin "2") (pinfunction "2_2") (pintype "passive"))
      (node (ref "JP3") (pin "3") (pinfunction "3_3") (pintype "passive"))
      (node (ref "PICKIT3") (pin "2") (pinfunction "2_2") (pintype "passive"))
      (node (ref "R16") (pin "1") (pinfunction "1_1") (pintype "passive"))
      (node (ref "R18") (pin "1") (pinfunction "1_1") (pintype "passive"))
      (node (ref "R19") (pin "1") (pinfunction "1_1") (pintype "passive"))
      (node (ref "R20") (pin "1") (pinfunction "1_1") (pintype "passive"))
      (node (ref "R21") (pin "1") (pinfunction "1_1") (pintype "passive"))
      (node (ref "R22") (pin "1") (pinfunction "1_1") (pintype "passive"))
      (node (ref "U$6") (pin "2") (pinfunction "3.3V_2") (pintype "bidirectional"))
      (node (ref "U$6") (pin "4") (pinfunction "PAD_4") (pintype "bidirectional"))
      (node (ref "U4") (pin "10") (pinfunction "VDD_10") (pintype "power_in"))
      (node (ref "U4") (pin "19") (pinfunction "AVDD_19") (pintype "power_in"))
      (node (ref "U4") (pin "26") (pinfunction "VDD_26") (pintype "power_in"))
      (node (ref "U4") (pin "35") (pinfunction "VUSB_35") (pintype "power_in"))
      (node (ref "U4") (pin "38") (pinfunction "VDD_38") (pintype "power_in"))
      (node (ref "U4") (pin "57") (pinfunction "ENVREG_57") (pintype "input"))
      (node (ref "U6") (pin "P$4") (pinfunction "I2C_VDD_P$4") (pintype "bidirectional"))
      (node (ref "U7") (pin "P$4") (pinfunction "I2C_VDD_P$4") (pintype "bidirectional"))
      (node (ref "U7") (pin "P$6") (pinfunction "ADR_P$6") (pintype "bidirectional"))
      (node (ref "U8") (pin "P$4") (pinfunction "I2C_VDD_P$4") (pintype "bidirectional"))
      (node (ref "U9") (pin "P$4") (pinfunction "I2C_VDD_P$4") (pintype "bidirectional"))
      (node (ref "U9") (pin "P$6") (pinfunction "ADR_P$6") (pintype "bidirectional"))
    )
    (net (code "2") (name "+5V") (class "Default")
      (node (ref "C1") (pin "1") (pinfunction "P$1_1") (pintype "passive"))
      (node (ref "J2") (pin "P1") (pinfunction "5V_P1") (pintype "bidirectional"))
      (node (ref "JP2") (pin "1") (pinfunction "1_1") (pintype "passive"))
      (node (ref "LED1") (pin "A") (pinfunction "A_A") (pintype "passive"))
      (node (ref "LED2") (pin "A") (pinfunction "A_A") (pintype "passive"))
      (node (ref "LED3") (pin "A") (pinfunction "A_A") (pintype "passive"))
      (node (ref "U1") (pin "1") (pinfunction "VDD1_1") (pintype "bidirectional"))
      (node (ref "U1") (pin "2") (pinfunction "VDD2_2") (pintype "bidirectional"))
    )
    (net (code "3") (name "/5V_USB") (class "Default")
      (node (ref "LED5") (pin "A") (pinfunction "A_A") (pintype "passive"))
      (node (ref "U$1") (pin "P1") (pinfunction "5V_P1") (pintype "bidirectional"))
      (node (ref "U$6") (pin "3") (pinfunction "5V_3") (pintype "bidirectional"))
      (node (ref "U4") (pin "34") (pinfunction "VBUS/RF7_34") (pintype "input"))
    )
    (net (code "4") (name "/BOOT") (class "Default")
      (node (ref "LED4") (pin "C") (pinfunction "C_C") (pintype "passive"))
      (node (ref "U4") (pin "39") (pinfunction "OSCI/CLKI/CN23/RC12_39") (pintype "bidirectional"))
    )
    (net (code "5") (name "/CHARGING") (class "Default")
      (node (ref "R1") (pin "2") (pinfunction "2_2") (pintype "passive"))
      (node (ref "U1") (pin "3") (pinfunction "STAT1_3") (pintype "bidirectional"))
    )
    (net (code "6") (name "/D+") (class "Default")
      (node (ref "U$1") (pin "P3") (pinfunction "D+_P3") (pintype "bidirectional"))
      (node (ref "U4") (pin "37") (pinfunction "D+/CN83/RG2_37") (pintype "bidirectional"))
    )
    (net (code "7") (name "/D-") (class "Default")
      (node (ref "U$1") (pin "P2") (pinfunction "D-_P2") (pintype "bidirectional"))
      (node (ref "U4") (pin "36") (pinfunction "D-/CN84/RG3_36") (pintype "bidirectional"))
    )
    (net (code "8") (name "/DONE") (class "Default")
      (node (ref "R2") (pin "2") (pinfunction "2_2") (pintype "passive"))
      (node (ref "U1") (pin "4") (pinfunction "STAT2_4") (pintype "bidirectional"))
    )
    (net (code "9") (name "/FAULT1") (class "Default")
      (node (ref "LED6") (pin "A") (pinfunction "A_A") (pintype "passive"))
      (node (ref "R23") (pin "2") (pinfunction "2_2") (pintype "passive"))
      (node (ref "U4") (pin "60") (pinfunction "GD0/CN58/RE0_60") (pintype "bidirectional"))
      (node (ref "U6") (pin "P$1") (pinfunction "FAULT_P$1") (pintype "bidirectional"))
    )
    (net (code "10") (name "/FAULT2") (class "Default")
      (node (ref "LED7") (pin "A") (pinfunction "A_A") (pintype "passive"))
      (node (ref "R24") (pin "2") (pinfunction "2_2") (pintype "passive"))
      (node (ref "U4") (pin "61") (pinfunction "GD1/CN59/RE1_61") (pintype "bidirectional"))
      (node (ref "U7") (pin "P$1") (pinfunction "FAULT_P$1") (pintype "bidirectional"))
    )
    (net (code "11") (name "/FAULT3") (class "Default")
      (node (ref "LED8") (pin "A") (pinfunction "A_A") (pintype "passive"))
      (node (ref "R25") (pin "2") (pinfunction "2_2") (pintype "passive"))
      (node (ref "U4") (pin "62") (pinfunction "GD2/CN60/RE2_62") (pintype "bidirectional"))
      (node (ref "U8") (pin "P$1") (pinfunction "FAULT_P$1") (pintype "bidirectional"))
    )
    (net (code "12") (name "/FAULT4") (class "Default")
      (node (ref "LED9") (pin "A") (pinfunction "A_A") (pintype "passive"))
      (node (ref "R26") (pin "2") (pinfunction "2_2") (pintype "passive"))
      (node (ref "U4") (pin "63") (pinfunction "GD3/CN61/RE3_63") (pintype "bidirectional"))
      (node (ref "U9") (pin "P$1") (pinfunction "FAULT_P$1") (pintype "bidirectional"))
    )
    (net (code "13") (name "/HOST") (class "Default")
      (node (ref "U4") (pin "40") (pinfunction "OSCO/CLKO/CN22/RC15_40") (pintype "bidirectional"))
    )
    (net (code "14") (name "/IN") (class "Default")
      (node (ref "R6") (pin "1") (pinfunction "1_1") (pintype "passive"))
      (node (ref "S1") (pin "C1") (pinfunction "C1_C1") (pintype "bidirectional"))
      (node (ref "S1") (pin "C2") (pinfunction "C2_C2") (pintype "bidirectional"))
      (node (ref "U2") (pin "IN") (pinfunction "INPUT_IN") (pintype "bidirectional"))
    )
    (net (code "15") (name "/LEFT") (class "Default")
      (node (ref "C29") (pin "2") (pinfunction "P$2_2") (pintype "passive"))
      (node (ref "C32") (pin "2") (pinfunction "P$2_2") (pintype "passive"))
      (node (ref "C35") (pin "2") (pinfunction "P$2_2") (pintype "passive"))
      (node (ref "C38") (pin "2") (pinfunction "P$2_2") (pintype "passive"))
      (node (ref "JP6") (pin "1") (pinfunction "1_1") (pintype "passive"))
    )
    (net (code "16") (name "/MCLR") (class "Default")
      (node (ref "PICKIT3") (pin "1") (pinfunction "1_1") (pintype "passive"))
      (node (ref "R18") (pin "2") (pinfunction "2_2") (pintype "passive"))
      (node (ref "R28") (pin "1") (pinfunction "1_1") (pintype "passive"))
    )
    (net (code "17") (name "/NGATE") (class "Default")
      (node (ref "Q1") (pin "4") (pinfunction "G_4") (pintype "passive"))
      (node (ref "U3") (pin "11") (pinfunction "NDRV_11") (pintype "output"))
    )
    (net (code "18") (name "/OUT-") (class "Default")
      (node (ref "JP9") (pin "P$2") (pinfunction "2_P$2") (pintype "passive"))
      (node (ref "U6") (pin "P$9") (pinfunction "OUTB_P$9") (pintype "bidirectional"))
    )
    (net (code "19") (name "/OUT1+") (class "Default")
      (node (ref "JP9") (pin "P$1") (pinfunction "1_P$1") (pintype "passive"))
      (node (ref "U6") (pin "P$7") (pinfunction "OUTA_P$7") (pintype "bidirectional"))
    )
    (net (code "20") (name "/OUT2+") (class "Default")
      (node (ref "JP11") (pin "P$1") (pinfunction "1_P$1") (pintype "passive"))
      (node (ref "U7") (pin "P$7") (pinfunction "OUTA_P$7") (pintype "bidirectional"))
    )
    (net (code "21") (name "/OUT2-") (class "Default")
      (node (ref "JP11") (pin "P$2") (pinfunction "2_P$2") (pintype "passive"))
      (node (ref "U7") (pin "P$9") (pinfunction "OUTB_P$9") (pintype "bidirectional"))
    )
    (net (code "22") (name "/OUT3+") (class "Default")
      (node (ref "JP12") (pin "P$1") (pinfunction "1_P$1") (pintype "passive"))
      (node (ref "U8") (pin "P$7") (pinfunction "OUTA_P$7") (pintype "bidirectional"))
    )
    (net (code "23") (name "/OUT3-") (class "Default")
      (node (ref "JP12") (pin "P$2") (pinfunction "2_P$2") (pintype "passive"))
      (node (ref "U8") (pin "P$9") (pinfunction "OUTB_P$9") (pintype "bidirectional"))
    )
    (net (code "24") (name "/OUT4+") (class "Default")
      (node (ref "JP13") (pin "P$1") (pinfunction "1_P$1") (pintype "passive"))
      (node (ref "U9") (pin "P$7") (pinfunction "OUTA_P$7") (pintype "bidirectional"))
    )
    (net (code "25") (name "/OUT4-") (class "Default")
      (node (ref "JP13") (pin "P$2") (pinfunction "2_P$2") (pintype "passive"))
      (node (ref "U9") (pin "P$9") (pinfunction "OUTB_P$9") (pintype "bidirectional"))
    )
    (net (code "26") (name "/PG") (class "Default")
      (node (ref "R3") (pin "2") (pinfunction "2_2") (pintype "passive"))
      (node (ref "U1") (pin "7") (pinfunction "PG_7") (pintype "bidirectional"))
    )
    (net (code "27") (name "/PGATE") (class "Default")
      (node (ref "Q2") (pin "4") (pinfunction "G_4") (pintype "passive"))
      (node (ref "U3") (pin "13") (pinfunction "PDRV_13") (pintype "output"))
    )
    (net (code "28") (name "/PGEC1") (class "Default")
      (node (ref "PICKIT3") (pin "5") (pinfunction "5_5") (pintype "passive"))
      (node (ref "U4") (pin "15") (pinfunction "PGEC1/AN1/VREF-/RP1/CN3/RB1_15") (pintype "bidirectional"))
    )
    (net (code "29") (name "/PGED1") (class "Default")
      (node (ref "PICKIT3") (pin "4") (pinfunction "4_4") (pintype "passive"))
      (node (ref "U4") (pin "16") (pinfunction "PGED1/AN0/VREF+/RP0/CN2/RB0_16") (pintype "bidirectional"))
    )
    (net (code "30") (name "/PIN3") (class "Default")
      (node (ref "U4") (pin "42") (pinfunction "RTCC/DMLN/RP2/CN53/RD8_42") (pintype "bidirectional"))
    )
    (net (code "31") (name "/PIN6") (class "Default")
      (node (ref "U4") (pin "45") (pinfunction "RP12/GD7/CN56/RD11_45") (pintype "bidirectional"))
    )
    (net (code "32") (name "/PIN7") (class "Default")
      (node (ref "U4") (pin "46") (pinfunction "DMH/RP11/INT0/CN49/RD0_46") (pintype "bidirectional"))
    )
    (net (code "33") (name "/PIN8") (class "Default")
      (node (ref "U4") (pin "47") (pinfunction "SOSCI/C3IND/CN1/RC13_47") (pintype "bidirectional"))
    )
    (net (code "34") (name "/PIN9") (class "Default")
      (node (ref "U4") (pin "48") (pinfunction "SOSCO/SCLKI/T1CK/C3INC/RPI37/CN0/RC14_48") (pintype "bidirectional"))
    )
    (net (code "35") (name "/PIN10") (class "Default")
      (node (ref "U4") (pin "49") (pinfunction "VCPCON/RP24/GD9/VBUSCHG/CN50/RD1_49") (pintype "bidirectional"))
    )
    (net (code "36") (name "/PIN11") (class "Default")
      (node (ref "U4") (pin "50") (pinfunction "DPH/RP23/CN51/RD2_50") (pintype "bidirectional"))
    )
    (net (code "37") (name "/PIN13") (class "Default")
      (node (ref "U4") (pin "52") (pinfunction "RP25/GCLK/CN13/RD4_52") (pintype "bidirectional"))
    )
    (net (code "38") (name "/PIN14") (class "Default")
      (node (ref "U4") (pin "53") (pinfunction "RP20/GPWR/CN14/RD5_53") (pintype "bidirectional"))
    )
    (net (code "39") (name "/PIN15") (class "Default")
      (node (ref "U4") (pin "54") (pinfunction "C3INB/CN15/RD6_54") (pintype "bidirectional"))
    )
    (net (code "40") (name "/PIN16") (class "Default")
      (node (ref "U4") (pin "55") (pinfunction "C3INA/SESSEND/CN16/RD7_55") (pintype "bidirectional"))
    )
    (net (code "41") (name "/PIN17") (class "Default")
      (node (ref "U4") (pin "58") (pinfunction "GD10/VBUSST/VCMPST1/VBUSVLD/CN68/RF0_58") (pintype "bidirectional"))
    )
    (net (code "42") (name "/PIN18") (class "Default")
      (node (ref "U4") (pin "59") (pinfunction "GD11/VCMPST2/SESSVLD/CN69/RF1_59") (pintype "bidirectional"))
    )
    (net (code "43") (name "/PIN23") (class "Default")
      (node (ref "U4") (pin "64") (pinfunction "HSYNC/CN62/RE4_64") (pintype "bidirectional"))
    )
    (net (code "44") (name "/PIN24") (class "Default")
      (node (ref "JP1") (pin "6") (pinfunction "6_6") (pintype "passive"))
      (node (ref "U4") (pin "1") (pinfunction "VSYNC/CN63/RE5_1") (pintype "bidirectional"))
    )
    (net (code "45") (name "/PIN25") (class "Default")
      (node (ref "JP1") (pin "5") (pinfunction "5_5") (pintype "passive"))
      (node (ref "U4") (pin "2") (pinfunction "GD12/SCL3/CN64/RE6_2") (pintype "bidirectional"))
    )
    (net (code "46") (name "/PIN26") (class "Default")
      (node (ref "JP1") (pin "4") (pinfunction "4_4") (pintype "passive"))
      (node (ref "U4") (pin "3") (pinfunction "GD13/SDA3/CN65/RE7_3") (pintype "bidirectional"))
    )
    (net (code "47") (name "/PIN27") (class "Default")
      (node (ref "JP1") (pin "3") (pinfunction "3_3") (pintype "passive"))
      (node (ref "U4") (pin "4") (pinfunction "C1IND/RP21/CN8/RG6_4") (pintype "bidirectional"))
    )
    (net (code "48") (name "/PIN28") (class "Default")
      (node (ref "JP1") (pin "2") (pinfunction "2_2") (pintype "passive"))
      (node (ref "U4") (pin "5") (pinfunction "C1INC/RP26/CN9/RG7_5") (pintype "bidirectional"))
    )
    (net (code "49") (name "/PIN29") (class "Default")
      (node (ref "JP1") (pin "1") (pinfunction "1_1") (pintype "passive"))
      (node (ref "U4") (pin "6") (pinfunction "C2IND/RP19/GD14/CN10/RG8_6") (pintype "bidirectional"))
    )
    (net (code "50") (name "/PIN30") (class "Default")
      (node (ref "U4") (pin "8") (pinfunction "C2INC/RP27/GD15/CN11/RG9_8") (pintype "bidirectional"))
    )
    (net (code "51") (name "/PIN31") (class "Default")
      (node (ref "U4") (pin "11") (pinfunction "PGEC3/AN5/C1INA/VBUSON/RP18/CN7/RB5_11") (pintype "bidirectional"))
    )
    (net (code "52") (name "/PIN32") (class "Default")
      (node (ref "U4") (pin "12") (pinfunction "PGED3/AN4/C1INB/USBOEN/RP28/CN6/RB4_12") (pintype "bidirectional"))
    )
    (net (code "53") (name "/PIN33") (class "Default")
      (node (ref "U4") (pin "13") (pinfunction "AN3/C2INA/VPIO/CN5/RB3_13") (pintype "bidirectional"))
    )
    (net (code "54") (name "/PIN34") (class "Default")
      (node (ref "U4") (pin "14") (pinfunction "AN2/C2INB/VMIO/RP13/CN4/RB2_14") (pintype "bidirectional"))
    )
    (net (code "55") (name "/PIN37") (class "Default")
      (node (ref "JP10") (pin "6") (pinfunction "6_6") (pintype "passive"))
      (node (ref "U4") (pin "17") (pinfunction "PGEC2/AN6/RP6/CN24/RB6_17") (pintype "bidirectional"))
    )
    (net (code "56") (name "/PIN38") (class "Default")
      (node (ref "JP10") (pin "5") (pinfunction "5_5") (pintype "passive"))
      (node (ref "U4") (pin "18") (pinfunction "PGED2/AN7/RP7/RCV/CN25/RB7_18") (pintype "bidirectional"))
    )
    (net (code "57") (name "/PIN39") (class "Default")
      (node (ref "JP10") (pin "4") (pinfunction "4_4") (pintype "passive"))
      (node (ref "U4") (pin "21") (pinfunction "AN8/RP8/CN26/RB8_21") (pintype "bidirectional"))
    )
    (net (code "58") (name "/PIN40") (class "Default")
      (node (ref "JP10") (pin "3") (pinfunction "3_3") (pintype "passive"))
      (node (ref "U4") (pin "22") (pinfunction "AN9/RP9/CN27/RB9_22") (pintype "bidirectional"))
    )
    (net (code "59") (name "/PIN41") (class "Default")
      (node (ref "JP10") (pin "2") (pinfunction "2_2") (pintype "passive"))
      (node (ref "U4") (pin "23") (pinfunction "TMS/CVREF/AN10/CN28/RB10_23") (pintype "bidirectional"))
    )
    (net (code "60") (name "/PIN42") (class "Default")
      (node (ref "JP10") (pin "1") (pinfunction "1_1") (pintype "passive"))
      (node (ref "U4") (pin "24") (pinfunction "TDO/AN11/CN29/RB11_24") (pintype "bidirectional"))
    )
    (net (code "61") (name "/PIN43") (class "Default")
      (node (ref "JP14") (pin "6") (pinfunction "6_6") (pintype "passive"))
      (node (ref "U4") (pin "27") (pinfunction "TCK/AN12/CTEDG2/CN30/RB12_27") (pintype "bidirectional"))
    )
    (net (code "62") (name "/PIN44") (class "Default")
      (node (ref "JP14") (pin "5") (pinfunction "5_5") (pintype "passive"))
      (node (ref "U4") (pin "28") (pinfunction "TDI/AN13/CTEDG1/CN31/RB13_28") (pintype "bidirectional"))
    )
    (net (code "63") (name "/PIN45") (class "Default")
      (node (ref "JP14") (pin "4") (pinfunction "4_4") (pintype "passive"))
      (node (ref "U4") (pin "29") (pinfunction "AN14/CTPLS/RP14/CN32/RB14_29") (pintype "bidirectional"))
    )
    (net (code "64") (name "/PIN46") (class "Default")
      (node (ref "JP14") (pin "3") (pinfunction "3_3") (pintype "passive"))
      (node (ref "U4") (pin "30") (pinfunction "AN15/RP29/REFO/CN12/RB15_30") (pintype "bidirectional"))
    )
    (net (code "65") (name "/PROG") (class "Default")
      (node (ref "R4") (pin "2") (pinfunction "2_2") (pintype "passive"))
      (node (ref "U1") (pin "6") (pinfunction "PROG_6") (pintype "bidirectional"))
    )
    (net (code "66") (name "/PWMOUT") (class "Default")
      (node (ref "JP8") (pin "2") (pinfunction "2_2") (pintype "passive"))
      (node (ref "R27") (pin "1") (pinfunction "1_1") (pintype "passive"))
      (node (ref "U4") (pin "51") (pinfunction "RP22/GEN/CN52/RD3_51") (pintype "bidirectional"))
      (node (ref "U5") (pin "P3") (pinfunction "IN_P3") (pintype "bidirectional"))
    )
    (net (code "67") (name "/RIGHT") (class "Default")
      (node (ref "C28") (pin "2") (pinfunction "P$2_2") (pintype "passive"))
      (node (ref "C31") (pin "2") (pinfunction "P$2_2") (pintype "passive"))
      (node (ref "C34") (pin "2") (pinfunction "P$2_2") (pintype "passive"))
      (node (ref "C37") (pin "2") (pinfunction "P$2_2") (pintype "passive"))
      (node (ref "JP6") (pin "3") (pinfunction "3_3") (pintype "passive"))
    )
    (net (code "68") (name "/SCL0") (class "Default")
      (node (ref "R19") (pin "2") (pinfunction "2_2") (pintype "passive"))
      (node (ref "U4") (pin "44") (pinfunction "SCL1/RP3/GD6/CN55/RD10_44") (pintype "bidirectional"))
      (node (ref "U6") (pin "P$2") (pinfunction "SCL_P$2") (pintype "bidirectional"))
      (node (ref "U7") (pin "P$2") (pinfunction "SCL_P$2") (pintype "bidirectional"))
    )
    (net (code "69") (name "/SCL1") (class "Default")
      (node (ref "JP14") (pin "1") (pinfunction "1_1") (pintype "passive"))
      (node (ref "R21") (pin "2") (pinfunction "2_2") (pintype "passive"))
      (node (ref "U4") (pin "32") (pinfunction "SCL2/RP17/GD5/CN18/RF5_32") (pintype "bidirectional"))
      (node (ref "U8") (pin "P$2") (pinfunction "SCL_P$2") (pintype "bidirectional"))
      (node (ref "U9") (pin "P$2") (pinfunction "SCL_P$2") (pintype "bidirectional"))
    )
    (net (code "70") (name "/SDA0") (class "Default")
      (node (ref "R20") (pin "2") (pinfunction "2_2") (pintype "passive"))
      (node (ref "U4") (pin "43") (pinfunction "DPLN/SDA1/RP4/GD8/CN54/RD9_43") (pintype "bidirectional"))
      (node (ref "U6") (pin "P$3") (pinfunction "SDA_P$3") (pintype "bidirectional"))
      (node (ref "U7") (pin "P$3") (pinfunction "SDA_P$3") (pintype "bidirectional"))
    )
    (net (code "71") (name "/SDA1") (class "Default")
      (node (ref "JP14") (pin "2") (pinfunction "2_2") (pintype "passive"))
      (node (ref "R22") (pin "2") (pinfunction "2_2") (pintype "passive"))
      (node (ref "U4") (pin "31") (pinfunction "SDA2/RP10/GD4/CN17/RF4_31") (pintype "bidirectional"))
      (node (ref "U8") (pin "P$3") (pinfunction "SDA_P$3") (pintype "bidirectional"))
      (node (ref "U9") (pin "P$3") (pinfunction "SDA_P$3") (pintype "bidirectional"))
    )
    (net (code "72") (name "/SWITCH+") (class "Default")
      (node (ref "D1") (pin "A1") (pinfunction "A1_A1") (pintype "passive"))
      (node (ref "D1") (pin "A2") (pinfunction "A2_A2") (pintype "passive"))
      (node (ref "L1") (pin "P1") (pinfunction "1_P1") (pintype "bidirectional"))
      (node (ref "Q1") (pin "5") (pinfunction "D_2_5") (pintype "passive"))
      (node (ref "Q1") (pin "6") (pinfunction "D_3_6") (pintype "passive"))
      (node (ref "Q1") (pin "7") (pinfunction "D_4_7") (pintype "passive"))
      (node (ref "Q1") (pin "8") (pinfunction "D_8") (pintype "passive"))
      (node (ref "Q1") (pin "PAD") (pinfunction "PAD_PAD") (pintype "bidirectional"))
      (node (ref "Q2") (pin "1") (pinfunction "D_2_1") (pintype "passive"))
      (node (ref "Q2") (pin "2") (pinfunction "D_3_2") (pintype "passive"))
      (node (ref "Q2") (pin "3") (pinfunction "D_3") (pintype "passive"))
      (node (ref "R7") (pin "2") (pinfunction "2_2") (pintype "passive"))
      (node (ref "R8") (pin "2") (pinfunction "2_2") (pintype "passive"))
      (node (ref "R9") (pin "2") (pinfunction "2_2") (pintype "passive"))
    )
    (net (code "73") (name "/THERMAL") (class "Default")
      (node (ref "R5") (pin "2") (pinfunction "2_2") (pintype "passive"))
      (node (ref "U1") (pin "8") (pinfunction "THERM_8") (pintype "bidirectional"))
    )
    (net (code "74") (name "GND") (class "Default")
      (node (ref "C10") (pin "2") (pinfunction "2_2") (pintype "passive"))
      (node (ref "C11") (pin "2") (pinfunction "2_2") (pintype "passive"))
      (node (ref "C12") (pin "2") (pinfunction "2_2") (pintype "passive"))
      (node (ref "C16") (pin "1") (pinfunction "1_1") (pintype "passive"))
      (node (ref "C17") (pin "1") (pinfunction "1_1") (pintype "passive"))
      (node (ref "C18") (pin "1") (pinfunction "1_1") (pintype "passive"))
      (node (ref "C19") (pin "1") (pinfunction "1_1") (pintype "passive"))
      (node (ref "C20") (pin "2") (pinfunction "P$2_2") (pintype "passive"))
      (node (ref "C21") (pin "1") (pinfunction "1_1") (pintype "passive"))
      (node (ref "C22") (pin "2") (pinfunction "2_2") (pintype "passive"))
      (node (ref "C23") (pin "2") (pinfunction "P$2_2") (pintype "passive"))
      (node (ref "C24") (pin "2") (pinfunction "2_2") (pintype "passive"))
      (node (ref "C25") (pin "2") (pinfunction "2_2") (pintype "passive"))
      (node (ref "C26") (pin "1") (pinfunction "1_1") (pintype "passive"))
      (node (ref "C27") (pin "2") (pinfunction "P$2_2") (pintype "passive"))
      (node (ref "C3") (pin "2") (pinfunction "2_2") (pintype "passive"))
      (node (ref "C30") (pin "2") (pinfunction "P$2_2") (pintype "passive"))
      (node (ref "C33") (pin "2") (pinfunction "P$2_2") (pintype "passive"))
      (node (ref "C36") (pin "2") (pinfunction "P$2_2") (pintype "passive"))
      (node (ref "C39") (pin "1") (pinfunction "1_1") (pintype "passive"))
      (node (ref "C4") (pin "-") (pinfunction "-_-") (pintype "bidirectional"))
      (node (ref "C40") (pin "2") (pinfunction "P$2_2") (pintype "passive"))
      (node (ref "C41") (pin "2") (pinfunction "P$2_2") (pintype "passive"))
      (node (ref "C42") (pin "2") (pinfunction "P$2_2") (pintype "passive"))
      (node (ref "C43") (pin "2") (pinfunction "P$2_2") (pintype "passive"))
      (node (ref "C44") (pin "2") (pinfunction "P$2_2") (pintype "passive"))
      (node (ref "C45") (pin "2") (pinfunction "P$2_2") (pintype "passive"))
      (node (ref "C46") (pin "2") (pinfunction "P$2_2") (pintype "passive"))
      (node (ref "C47") (pin "2") (pinfunction "P$2_2") (pintype "passive"))
      (node (ref "C48") (pin "2") (pinfunction "2_2") (pintype "passive"))
      (node (ref "C5") (pin "-") (pinfunction "-_-") (pintype "bidirectional"))
      (node (ref "C6") (pin "2") (pinfunction "2_2") (pintype "passive"))
      (node (ref "C7") (pin "2") (pinfunction "2_2") (pintype "passive"))
      (node (ref "C8") (pin "2") (pinfunction "2_2") (pintype "passive"))
      (node (ref "J3") (pin "GND") (pinfunction "GND_GND") (pintype "bidirectional"))
      (node (ref "J3") (pin "GNDBREAK") (pinfunction "GNDBREAK_GNDBREAK") (pintype "bidirectional"))
      (node (ref "JP5") (pin "1") (pinfunction "1_1") (pintype "passive"))
      (node (ref "JP5") (pin "2") (pinfunction "2_2") (pintype "passive"))
      (node (ref "JP5") (pin "3") (pinfunction "3_3") (pintype "passive"))
      (node (ref "JP6") (pin "2") (pinfunction "2_2") (pintype "passive"))
      (node (ref "JP7") (pin "P$2") (pinfunction "2_P$2") (pintype "passive"))
      (node (ref "JP8") (pin "1") (pinfunction "1_1") (pintype "passive"))
      (node (ref "LED6") (pin "C") (pinfunction "C_C") (pintype "passive"))
      (node (ref "LED7") (pin "C") (pinfunction "C_C") (pintype "passive"))
      (node (ref "LED8") (pin "C") (pinfunction "C_C") (pintype "passive"))
      (node (ref "LED9") (pin "C") (pinfunction "C_C") (pintype "passive"))
      (node (ref "PICKIT3") (pin "3") (pinfunction "3_3") (pintype "passive"))
      (node (ref "Q1") (pin "1") (pinfunction "S_2_1") (pintype "passive"))
      (node (ref "Q1") (pin "2") (pinfunction "S_3_2") (pintype "passive"))
      (node (ref "Q1") (pin "3") (pinfunction "S_3") (pintype "passive"))
      (node (ref "R12") (pin "1") (pinfunction "1_1") (pintype "passive"))
      (node (ref "R14") (pin "2") (pinfunction "2_2") (pintype "passive"))
      (node (ref "R17") (pin "2") (pinfunction "2_2") (pintype "passive"))
      (node (ref "R27") (pin "2") (pinfunction "2_2") (pintype "passive"))
      (node (ref "U$1") (pin "P4") (pinfunction "GND_P4") (pintype "bidirectional"))
      (node (ref "U$1") (pin "S1") (pinfunction "S1_S1") (pintype "bidirectional"))
      (node (ref "U$1") (pin "S2") (pinfunction "S2_S2") (pintype "bidirectional"))
      (node (ref "U$4") (pin "S2") (pinfunction "S2_S2") (pintype "bidirectional"))
      (node (ref "U$5") (pin "S") (pinfunction "S_S") (pintype "bidirectional"))
      (node (ref "U$6") (pin "1") (pinfunction "GND_1") (pintype "bidirectional"))
      (node (ref "U2") (pin "D1") (pinfunction "DRAIN_D1") (pintype "bidirectional"))
      (node (ref "U2") (pin "D2") (pinfunction "TAB_D2") (pintype "bidirectional"))
      (node (ref "U3") (pin "1") (pinfunction "SYNC/SD_1") (pintype "input"))
      (node (ref "U3") (pin "12") (pinfunction "GND_12") (pintype "power_in"))
      (node (ref "U3") (pin "2") (pinfunction "CCS_2") (pintype "input"))
      (node (ref "U3") (pin "5") (pinfunction "BUCK_5") (pintype "input"))
      (node (ref "U4") (pin "20") (pinfunction "AVSS_20") (pintype "power_in"))
      (node (ref "U4") (pin "25") (pinfunction "VSS_25") (pintype "power_in"))
      (node (ref "U4") (pin "33") (pinfunction "RP16/USBID/CN71/RF3_33") (pintype "bidirectional"))
      (node (ref "U4") (pin "41") (pinfunction "VSS_41") (pintype "power_in"))
      (node (ref "U4") (pin "9") (pinfunction "VSS_9") (pintype "power_in"))
      (node (ref "U5") (pin "P1") (pinfunction "NC_P1") (pintype "bidirectional"))
      (node (ref "U5") (pin "P4") (pinfunction "GND_P4") (pintype "bidirectional"))
      (node (ref "U6") (pin "P$15") (pinfunction "PAD_P$15") (pintype "bidirectional"))
      (node (ref "U6") (pin "P$5") (pinfunction "GND_P$5") (pintype "bidirectional"))
      (node (ref "U6") (pin "P$6") (pinfunction "ADR_P$6") (pintype "bidirectional"))
      (node (ref "U6") (pin "P$8") (pinfunction "PGND_P$8") (pintype "bidirectional"))
      (node (ref "U7") (pin "P$15") (pinfunction "PAD_P$15") (pintype "bidirectional"))
      (node (ref "U7") (pin "P$5") (pinfunction "GND_P$5") (pintype "bidirectional"))
      (node (ref "U7") (pin "P$8") (pinfunction "PGND_P$8") (pintype "bidirectional"))
      (node (ref "U8") (pin "P$15") (pinfunction "PAD_P$15") (pintype "bidirectional"))
      (node (ref "U8") (pin "P$5") (pinfunction "GND_P$5") (pintype "bidirectional"))
      (node (ref "U8") (pin "P$6") (pinfunction "ADR_P$6") (pintype "bidirectional"))
      (node (ref "U8") (pin "P$8") (pinfunction "PGND_P$8") (pintype "bidirectional"))
      (node (ref "U9") (pin "P$15") (pinfunction "PAD_P$15") (pintype "bidirectional"))
      (node (ref "U9") (pin "P$5") (pinfunction "GND_P$5") (pintype "bidirectional"))
      (node (ref "U9") (pin "P$8") (pinfunction "PGND_P$8") (pintype "bidirectional"))
    )
    (net (code "75") (name "Net-(C3-Pad1)") (class "Default")
      (node (ref "C3") (pin "1") (pinfunction "1_1") (pintype "passive"))
      (node (ref "R8") (pin "1") (pinfunction "1_1") (pintype "passive"))
    )
    (net (code "76") (name "Net-(C9-Pad1)") (class "Default")
      (node (ref "C9") (pin "1") (pinfunction "1_1") (pintype "passive"))
      (node (ref "R9") (pin "1") (pinfunction "1_1") (pintype "passive"))
    )
    (net (code "77") (name "Net-(C13-Pad2)") (class "Default")
      (node (ref "C13") (pin "2") (pinfunction "2_2") (pintype "passive"))
      (node (ref "R11") (pin "1") (pinfunction "1_1") (pintype "passive"))
    )
    (net (code "78") (name "Net-(C14-Pad1)") (class "Default")
      (node (ref "C14") (pin "1") (pinfunction "1_1") (pintype "passive"))
      (node (ref "R13") (pin "2") (pinfunction "2_2") (pintype "passive"))
    )
    (net (code "79") (name "Net-(C20-P$1)") (class "Default")
      (node (ref "C20") (pin "1") (pinfunction "P$1_1") (pintype "passive"))
      (node (ref "U4") (pin "56") (pinfunction "VCAP_56") (pintype "power_in"))
    )
    (net (code "80") (name "Net-(C27-P$1)") (class "Default")
      (node (ref "C27") (pin "1") (pinfunction "P$1_1") (pintype "passive"))
      (node (ref "U6") (pin "P$13") (pinfunction "BIAS_P$13") (pintype "bidirectional"))
    )
    (net (code "81") (name "Net-(C28-P$1)") (class "Default")
      (node (ref "C28") (pin "1") (pinfunction "P$1_1") (pintype "passive"))
      (node (ref "U6") (pin "P$11") (pinfunction "IN2_P$11") (pintype "bidirectional"))
    )
    (net (code "82") (name "Net-(C29-P$1)") (class "Default")
      (node (ref "C29") (pin "1") (pinfunction "P$1_1") (pintype "passive"))
      (node (ref "U6") (pin "P$12") (pinfunction "IN1_P$12") (pintype "bidirectional"))
    )
    (net (code "83") (name "Net-(C30-P$1)") (class "Default")
      (node (ref "C30") (pin "1") (pinfunction "P$1_1") (pintype "passive"))
      (node (ref "U7") (pin "P$13") (pinfunction "BIAS_P$13") (pintype "bidirectional"))
    )
    (net (code "84") (name "Net-(C31-P$1)") (class "Default")
      (node (ref "C31") (pin "1") (pinfunction "P$1_1") (pintype "passive"))
      (node (ref "U7") (pin "P$11") (pinfunction "IN2_P$11") (pintype "bidirectional"))
    )
    (net (code "85") (name "Net-(C32-P$1)") (class "Default")
      (node (ref "C32") (pin "1") (pinfunction "P$1_1") (pintype "passive"))
      (node (ref "U7") (pin "P$12") (pinfunction "IN1_P$12") (pintype "bidirectional"))
    )
    (net (code "86") (name "Net-(C33-P$1)") (class "Default")
      (node (ref "C33") (pin "1") (pinfunction "P$1_1") (pintype "passive"))
      (node (ref "U8") (pin "P$13") (pinfunction "BIAS_P$13") (pintype "bidirectional"))
    )
    (net (code "87") (name "Net-(C34-P$1)") (class "Default")
      (node (ref "C34") (pin "1") (pinfunction "P$1_1") (pintype "passive"))
      (node (ref "U8") (pin "P$11") (pinfunction "IN2_P$11") (pintype "bidirectional"))
    )
    (net (code "88") (name "Net-(C35-P$1)") (class "Default")
      (node (ref "C35") (pin "1") (pinfunction "P$1_1") (pintype "passive"))
      (node (ref "U8") (pin "P$12") (pinfunction "IN1_P$12") (pintype "bidirectional"))
    )
    (net (code "89") (name "Net-(C36-P$1)") (class "Default")
      (node (ref "C36") (pin "1") (pinfunction "P$1_1") (pintype "passive"))
      (node (ref "U9") (pin "P$13") (pinfunction "BIAS_P$13") (pintype "bidirectional"))
    )
    (net (code "90") (name "Net-(C37-P$1)") (class "Default")
      (node (ref "C37") (pin "1") (pinfunction "P$1_1") (pintype "passive"))
      (node (ref "U9") (pin "P$11") (pinfunction "IN2_P$11") (pintype "bidirectional"))
    )
    (net (code "91") (name "Net-(C38-P$1)") (class "Default")
      (node (ref "C38") (pin "1") (pinfunction "P$1_1") (pintype "passive"))
      (node (ref "U9") (pin "P$12") (pinfunction "IN1_P$12") (pintype "bidirectional"))
    )
    (net (code "92") (name "Net-(JP7-1)") (class "Default")
      (node (ref "C22") (pin "1") (pinfunction "1_1") (pintype "passive"))
      (node (ref "C24") (pin "1") (pinfunction "1_1") (pintype "passive"))
      (node (ref "C25") (pin "1") (pinfunction "1_1") (pintype "passive"))
      (node (ref "JP7") (pin "P$1") (pinfunction "1_P$1") (pintype "passive"))
      (node (ref "U$4") (pin "S1") (pinfunction "S1_S1") (pintype "bidirectional"))
    )
    (net (code "93") (name "Net-(LED1-PadC)") (class "Default")
      (node (ref "LED1") (pin "C") (pinfunction "C_C") (pintype "passive"))
      (node (ref "R1") (pin "1") (pinfunction "1_1") (pintype "passive"))
    )
    (net (code "94") (name "Net-(LED2-PadC)") (class "Default")
      (node (ref "LED2") (pin "C") (pinfunction "C_C") (pintype "passive"))
      (node (ref "R2") (pin "1") (pinfunction "1_1") (pintype "passive"))
    )
    (net (code "95") (name "Net-(LED3-PadC)") (class "Default")
      (node (ref "LED3") (pin "C") (pinfunction "C_C") (pintype "passive"))
      (node (ref "R3") (pin "1") (pinfunction "1_1") (pintype "passive"))
    )
    (net (code "96") (name "Net-(LED4-PadA)") (class "Default")
      (node (ref "LED4") (pin "A") (pinfunction "A_A") (pintype "passive"))
      (node (ref "R16") (pin "2") (pinfunction "2_2") (pintype "passive"))
    )
    (net (code "97") (name "Net-(LED5-PadC)") (class "Default")
      (node (ref "LED5") (pin "C") (pinfunction "C_C") (pintype "passive"))
      (node (ref "R17") (pin "1") (pinfunction "1_1") (pintype "passive"))
    )
    (net (code "98") (name "Net-(R15-Pad1)") (class "Default")
      (node (ref "R15") (pin "1") (pinfunction "1_1") (pintype "passive"))
      (node (ref "U$5") (pin "G") (pinfunction "G_G") (pintype "bidirectional"))
    )
    (net (code "99") (name "Net-(U$4-PadP2)") (class "Default")
      (node (ref "U$4") (pin "P2") (pinfunction "P2_P2") (pintype "bidirectional"))
      (node (ref "U$5") (pin "D") (pinfunction "D_D") (pintype "bidirectional"))
    )
    (net (code "100") (name "Net-(U3-COMP)") (class "Default")
      (node (ref "C14") (pin "2") (pinfunction "2_2") (pintype "passive"))
      (node (ref "C15") (pin "2") (pinfunction "2_2") (pintype "passive"))
      (node (ref "U3") (pin "7") (pinfunction "COMP_7") (pintype "output"))
    )
    (net (code "101") (name "Net-(U3-FB)") (class "Default")
      (node (ref "C13") (pin "1") (pinfunction "1_1") (pintype "passive"))
      (node (ref "C15") (pin "1") (pinfunction "1_1") (pintype "passive"))
      (node (ref "R10") (pin "1") (pinfunction "1_1") (pintype "passive"))
      (node (ref "R12") (pin "2") (pinfunction "2_2") (pintype "passive"))
      (node (ref "R13") (pin "1") (pinfunction "1_1") (pintype "passive"))
      (node (ref "U3") (pin "8") (pinfunction "FB_8") (pintype "input"))
    )
    (net (code "102") (name "Net-(U3-RT)") (class "Default")
      (node (ref "R14") (pin "1") (pinfunction "1_1") (pintype "passive"))
      (node (ref "U3") (pin "3") (pinfunction "RT_3") (pintype "output"))
    )
    (net (code "103") (name "Net-(U3-SWN)") (class "Default")
      (node (ref "R7") (pin "1") (pinfunction "1_1") (pintype "passive"))
      (node (ref "U3") (pin "15") (pinfunction "SWP_15") (pintype "input"))
      (node (ref "U3") (pin "16") (pinfunction "SWN_16") (pintype "input"))
    )
    (net (code "104") (name "Net-(U4-~{MCLR})") (class "Default")
      (node (ref "R28") (pin "2") (pinfunction "2_2") (pintype "passive"))
      (node (ref "U4") (pin "7") (pinfunction "~{MCLR}_7") (pintype "input"))
    )
    (net (code "105") (name "Net-(U5-OUT)") (class "Default")
      (node (ref "R15") (pin "2") (pinfunction "2_2") (pintype "passive"))
      (node (ref "U5") (pin "P5") (pinfunction "OUT_P5") (pintype "bidirectional"))
    )
    (net (code "106") (name "V+") (class "Default")
      (node (ref "C10") (pin "1") (pinfunction "1_1") (pintype "passive"))
      (node (ref "C2") (pin "1") (pinfunction "P$1_1") (pintype "passive"))
      (node (ref "C4") (pin "+") (pinfunction "+_+") (pintype "bidirectional"))
      (node (ref "C6") (pin "1") (pinfunction "1_1") (pintype "passive"))
      (node (ref "J1") (pin "P2") (pinfunction "P2_P2") (pintype "bidirectional"))
      (node (ref "L1") (pin "P2") (pinfunction "2_P2") (pintype "bidirectional"))
      (node (ref "S1") (pin "A1") (pinfunction "A1_A1") (pintype "bidirectional"))
      (node (ref "S1") (pin "A2") (pinfunction "A2_A2") (pintype "bidirectional"))
      (node (ref "U1") (pin "10") (pinfunction "VBAT1_10") (pintype "bidirectional"))
      (node (ref "U1") (pin "9") (pinfunction "VBAT2_9") (pintype "bidirectional"))
      (node (ref "U3") (pin "4") (pinfunction "CCM_4") (pintype "input"))
      (node (ref "U3") (pin "6") (pinfunction "*PFM_6") (pintype "input"))
      (node (ref "U3") (pin "9") (pinfunction "VIN_9") (pintype "input"))
    )
    (net (code "107") (name "V-") (class "Default")
      (node (ref "C1") (pin "2") (pinfunction "P$2_2") (pintype "passive"))
      (node (ref "C2") (pin "2") (pinfunction "P$2_2") (pintype "passive"))
      (node (ref "J1") (pin "P1") (pinfunction "P1_P1") (pintype "bidirectional"))
      (node (ref "J2") (pin "P5") (pinfunction "GND_P5") (pintype "bidirectional"))
      (node (ref "JP2") (pin "2") (pinfunction "2_2") (pintype "passive"))
      (node (ref "R4") (pin "1") (pinfunction "1_1") (pintype "passive"))
      (node (ref "R5") (pin "1") (pinfunction "1_1") (pintype "passive"))
      (node (ref "R6") (pin "2") (pinfunction "2_2") (pintype "passive"))
      (node (ref "S1") (pin "B1") (pinfunction "B1_B1") (pintype "bidirectional"))
      (node (ref "S1") (pin "B2") (pinfunction "B2_B2") (pintype "bidirectional"))
      (node (ref "U1") (pin "5") (pinfunction "GND_5") (pintype "bidirectional"))
      (node (ref "U2") (pin "S") (pinfunction "SOURCE_S") (pintype "bidirectional"))
    )
    (net (code "108") (name "VCC") (class "Default")
      (node (ref "C11") (pin "1") (pinfunction "1_1") (pintype "passive"))
      (node (ref "C12") (pin "1") (pinfunction "1_1") (pintype "passive"))
      (node (ref "C26") (pin "2") (pinfunction "2_2") (pintype "passive"))
      (node (ref "C40") (pin "1") (pinfunction "P$1_1") (pintype "passive"))
      (node (ref "C41") (pin "1") (pinfunction "P$1_1") (pintype "passive"))
      (node (ref "C42") (pin "1") (pinfunction "P$1_1") (pintype "passive"))
      (node (ref "C43") (pin "1") (pinfunction "P$1_1") (pintype "passive"))
      (node (ref "C44") (pin "1") (pinfunction "P$1_1") (pintype "passive"))
      (node (ref "C45") (pin "1") (pinfunction "P$1_1") (pintype "passive"))
      (node (ref "C46") (pin "1") (pinfunction "P$1_1") (pintype "passive"))
      (node (ref "C47") (pin "1") (pinfunction "P$1_1") (pintype "passive"))
      (node (ref "C5") (pin "+") (pinfunction "+_+") (pintype "bidirectional"))
      (node (ref "C7") (pin "1") (pinfunction "1_1") (pintype "passive"))
      (node (ref "C8") (pin "1") (pinfunction "1_1") (pintype "passive"))
      (node (ref "C9") (pin "2") (pinfunction "2_2") (pintype "passive"))
      (node (ref "D1") (pin "C") (pinfunction "C_C") (pintype "passive"))
      (node (ref "J3") (pin "PWR") (pinfunction "PWR_PWR") (pintype "bidirectional"))
      (node (ref "JP4") (pin "1") (pinfunction "1_1") (pintype "passive"))
      (node (ref "JP4") (pin "2") (pinfunction "2_2") (pintype "passive"))
      (node (ref "JP4") (pin "3") (pinfunction "3_3") (pintype "passive"))
      (node (ref "JP8") (pin "3") (pinfunction "3_3") (pintype "passive"))
      (node (ref "Q2") (pin "5") (pinfunction "S_2_5") (pintype "passive"))
      (node (ref "Q2") (pin "6") (pinfunction "S_3_6") (pintype "passive"))
      (node (ref "Q2") (pin "7") (pinfunction "S_4_7") (pintype "passive"))
      (node (ref "Q2") (pin "8") (pinfunction "S_8") (pintype "passive"))
      (node (ref "Q2") (pin "PAD") (pinfunction "PAD_PAD") (pintype "bidirectional"))
      (node (ref "R10") (pin "2") (pinfunction "2_2") (pintype "passive"))
      (node (ref "R11") (pin "2") (pinfunction "2_2") (pintype "passive"))
      (node (ref "R23") (pin "1") (pinfunction "1_1") (pintype "passive"))
      (node (ref "R24") (pin "1") (pinfunction "1_1") (pintype "passive"))
      (node (ref "R25") (pin "1") (pinfunction "1_1") (pintype "passive"))
      (node (ref "R26") (pin "1") (pinfunction "1_1") (pintype "passive"))
      (node (ref "U$4") (pin "P1") (pinfunction "P1_P1") (pintype "bidirectional"))
      (node (ref "U3") (pin "10") (pinfunction "VOUT_10") (pintype "output"))
      (node (ref "U3") (pin "14") (pinfunction "VP_14") (pintype "input"))
      (node (ref "U5") (pin "P2") (pinfunction "VDD_P2") (pintype "bidirectional"))
      (node (ref "U6") (pin "P$10") (pinfunction "PVDD_P$10") (pintype "bidirectional"))
      (node (ref "U6") (pin "P$14") (pinfunction "VDD_P$14") (pintype "bidirectional"))
      (node (ref "U7") (pin "P$10") (pinfunction "PVDD_P$10") (pintype "bidirectional"))
      (node (ref "U7") (pin "P$14") (pinfunction "VDD_P$14") (pintype "bidirectional"))
      (node (ref "U8") (pin "P$10") (pinfunction "PVDD_P$10") (pintype "bidirectional"))
      (node (ref "U8") (pin "P$14") (pinfunction "VDD_P$14") (pintype "bidirectional"))
      (node (ref "U9") (pin "P$10") (pinfunction "PVDD_P$10") (pintype "bidirectional"))
      (node (ref "U9") (pin "P$14") (pinfunction "VDD_P$14") (pintype "bidirectional"))
    )
    (net (code "109") (name "unconnected-(J2-D+-PadP3)") (class "Default")
      (node (ref "J2") (pin "P3") (pinfunction "D+_P3") (pintype "bidirectional"))
    )
    (net (code "110") (name "unconnected-(J2-D--PadP2)") (class "Default")
      (node (ref "J2") (pin "P2") (pinfunction "D-_P2") (pintype "bidirectional"))
    )
    (net (code "111") (name "unconnected-(J2-ID-PadP4)") (class "Default")
      (node (ref "J2") (pin "P4") (pinfunction "ID_P4") (pintype "bidirectional"))
    )
  )
)
